# nexus5.net
KiCad netlist of a schematic drawn in Altium Designer
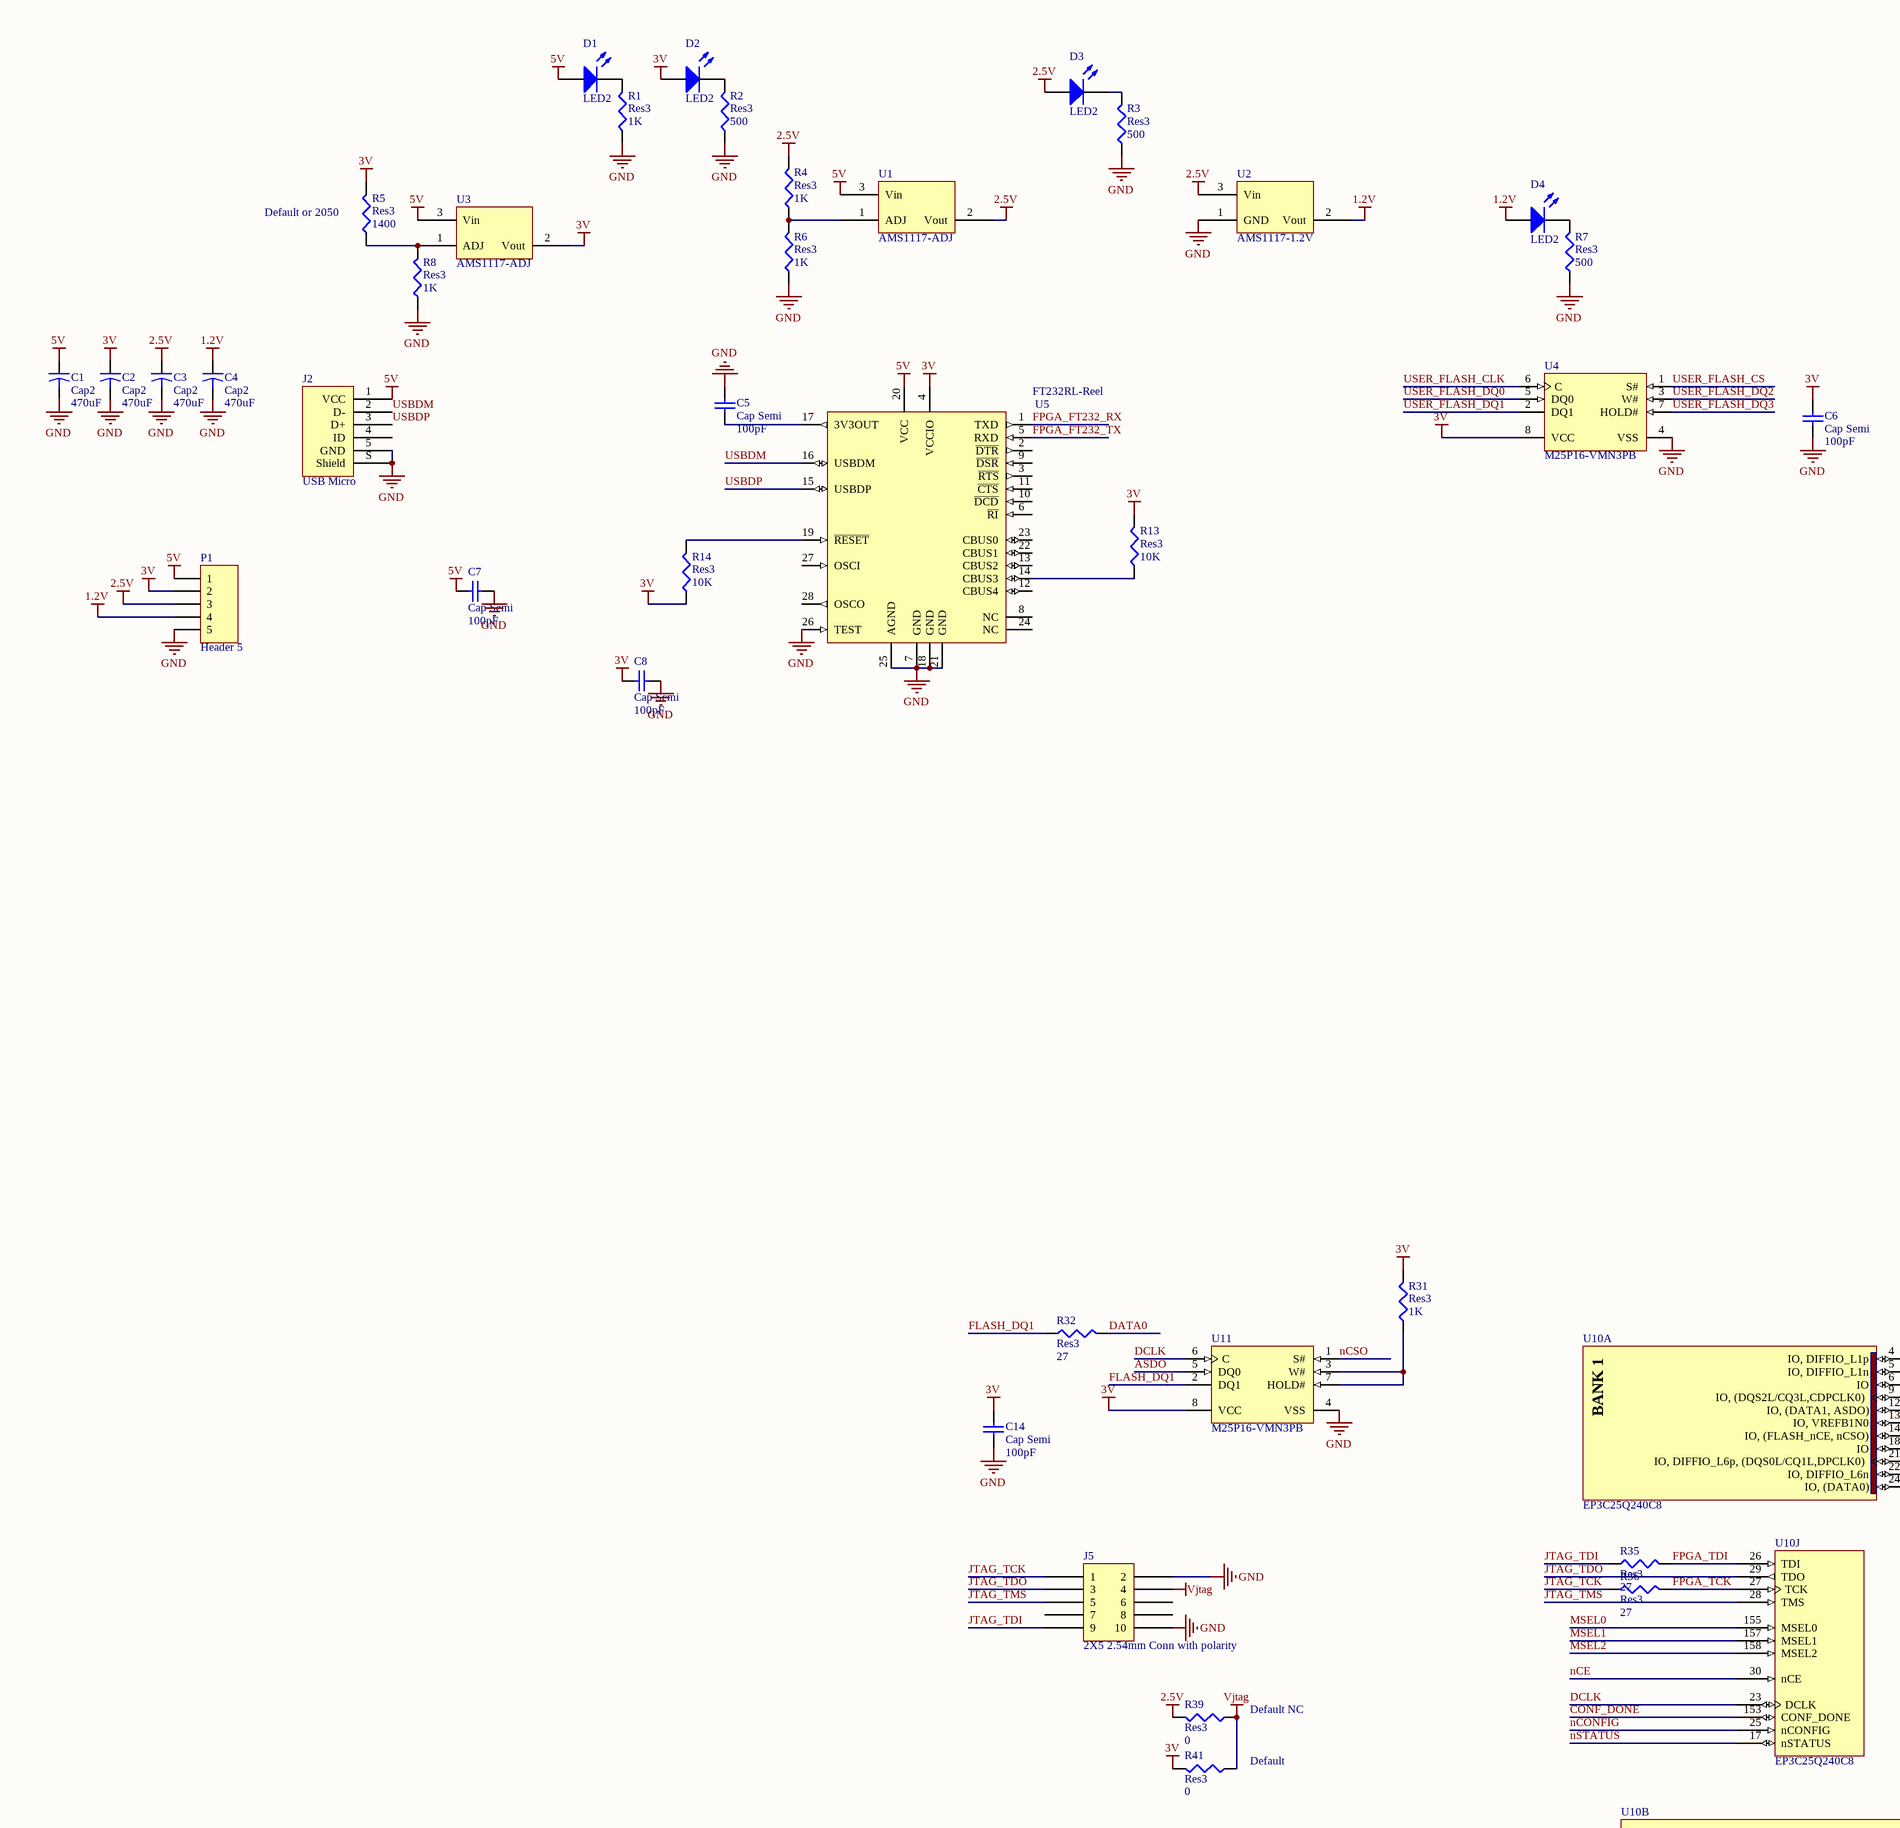
[diagram p0: nexus5.SchDoc, top left]
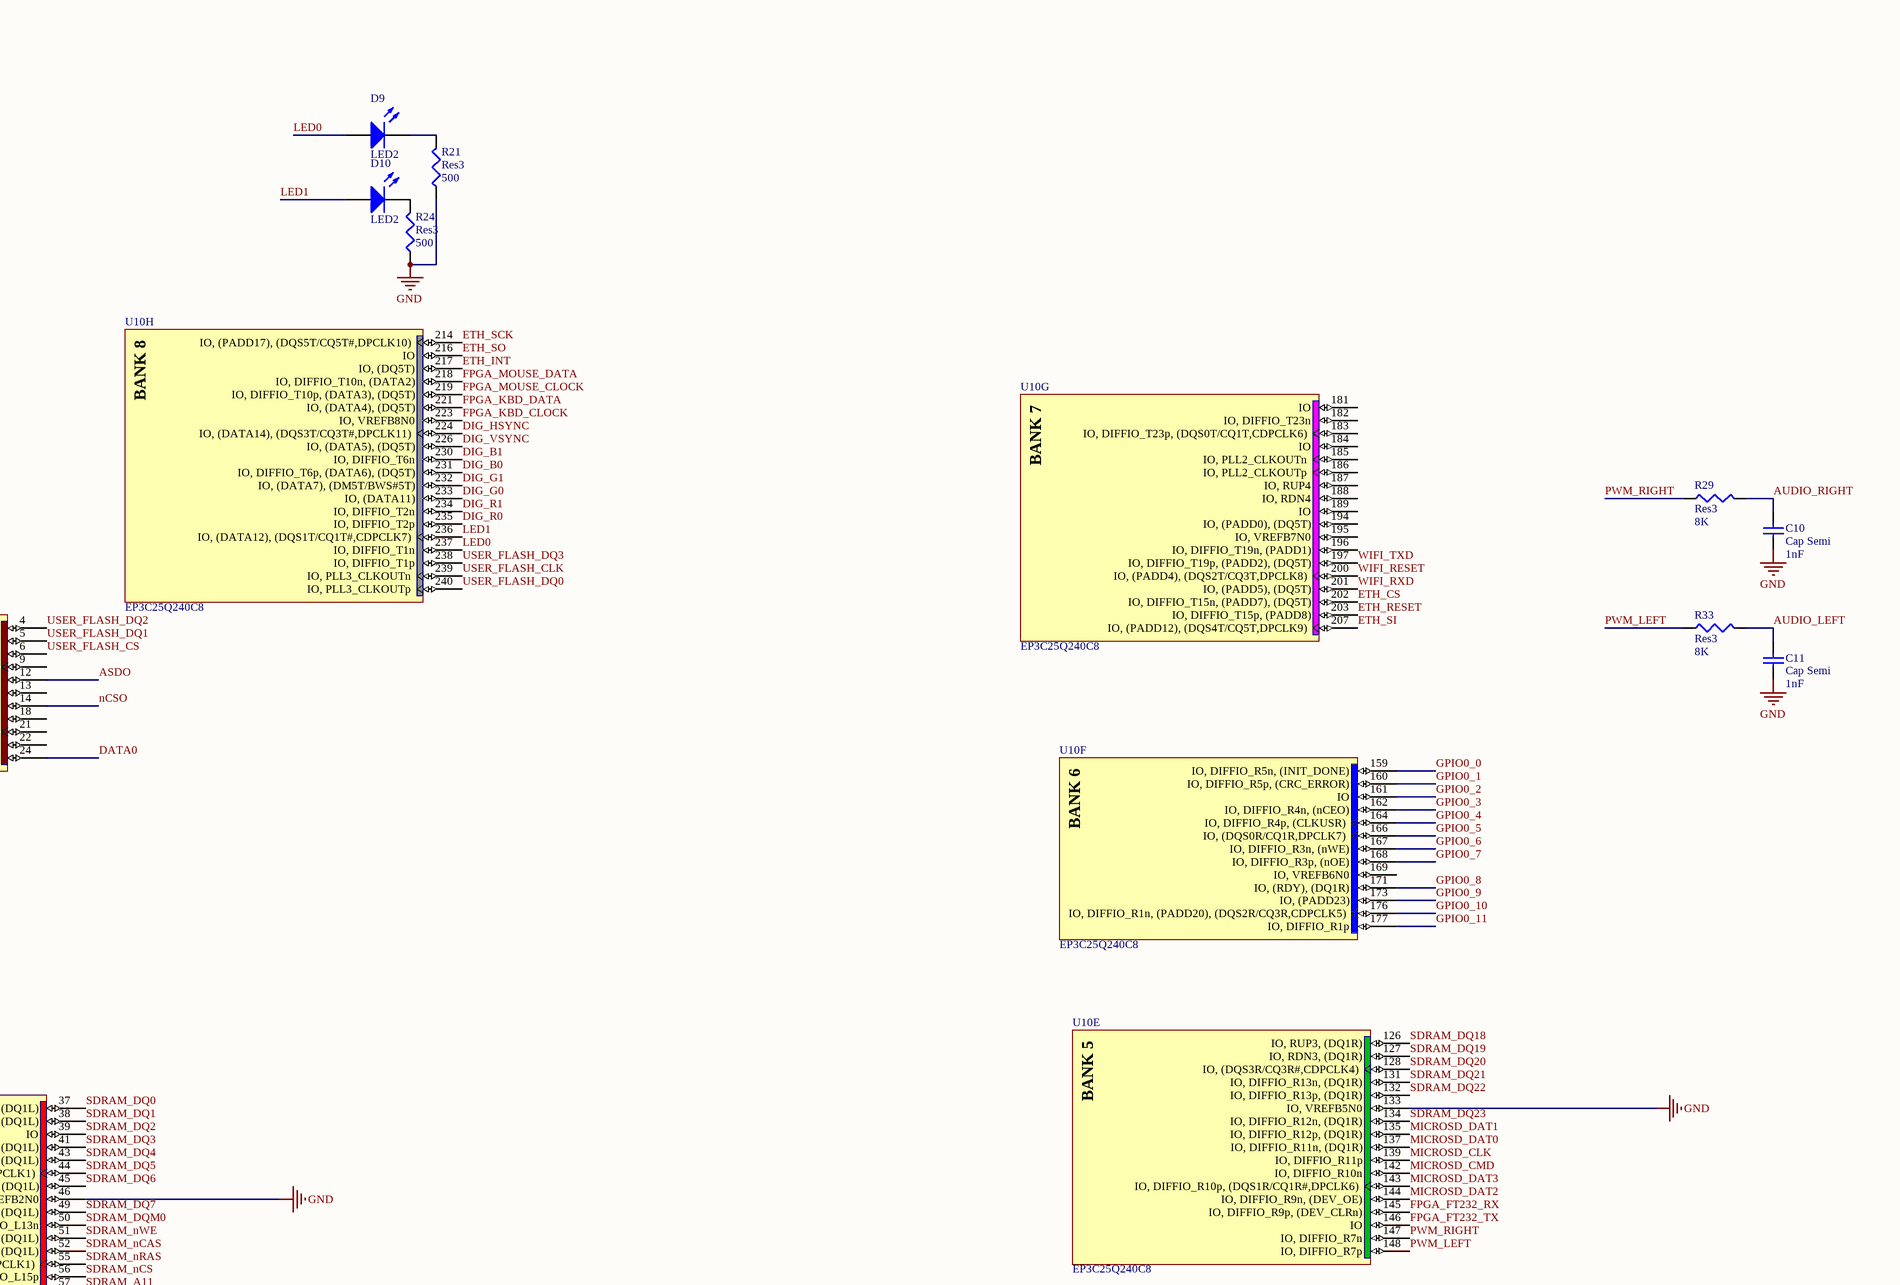
[diagram p1: nexus5.SchDoc, top middle]
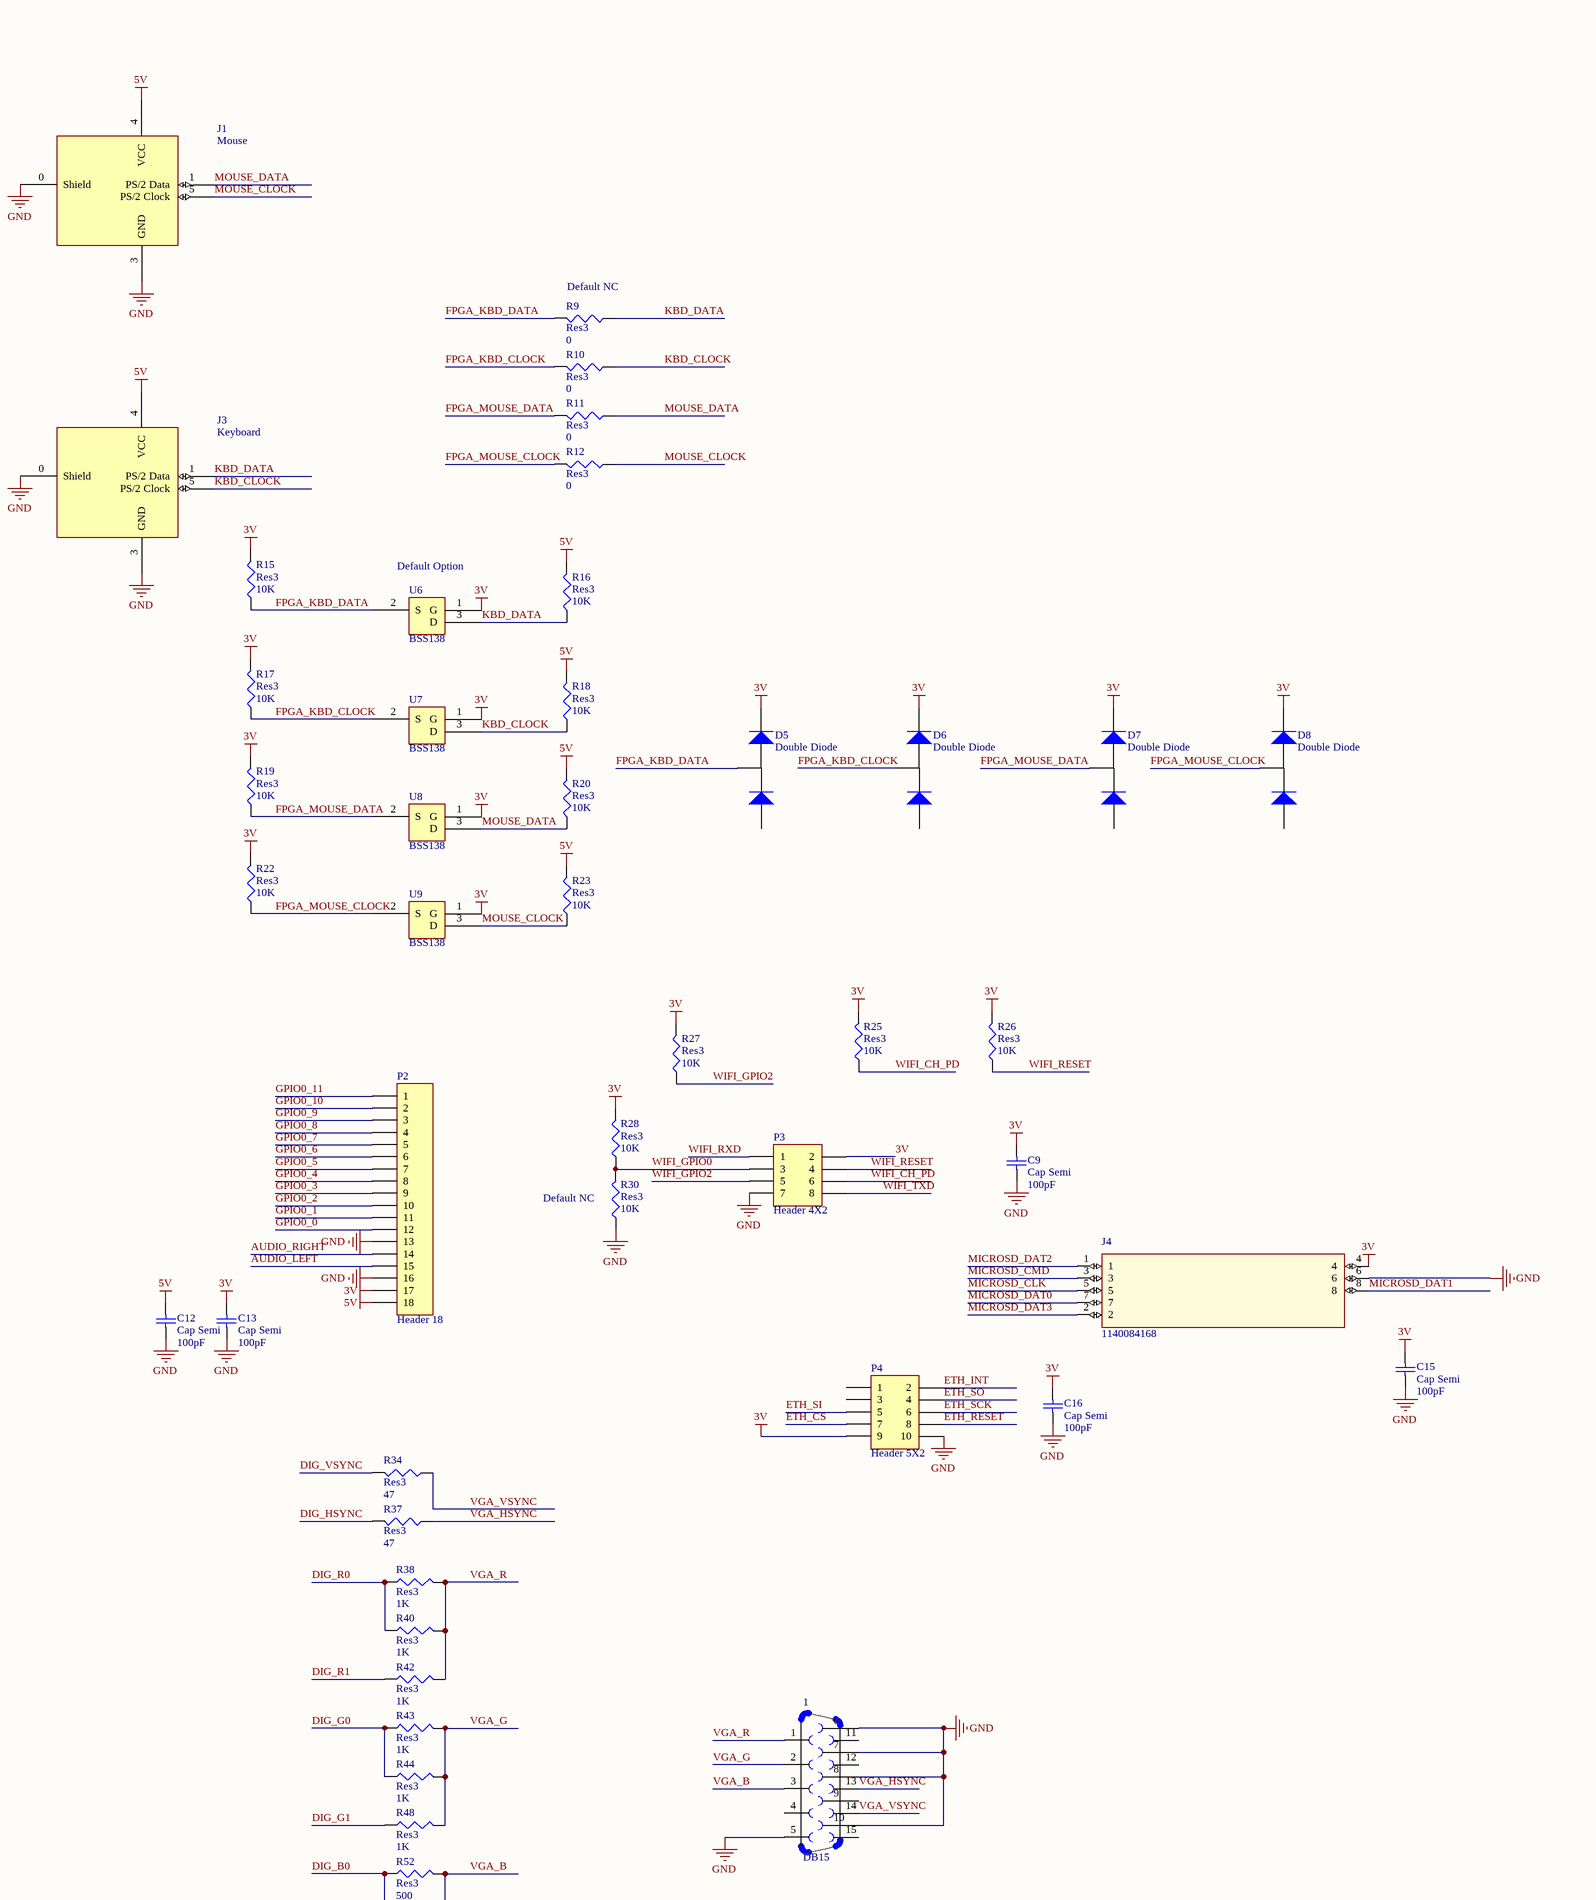
[diagram p2: nexus5.SchDoc, top right]
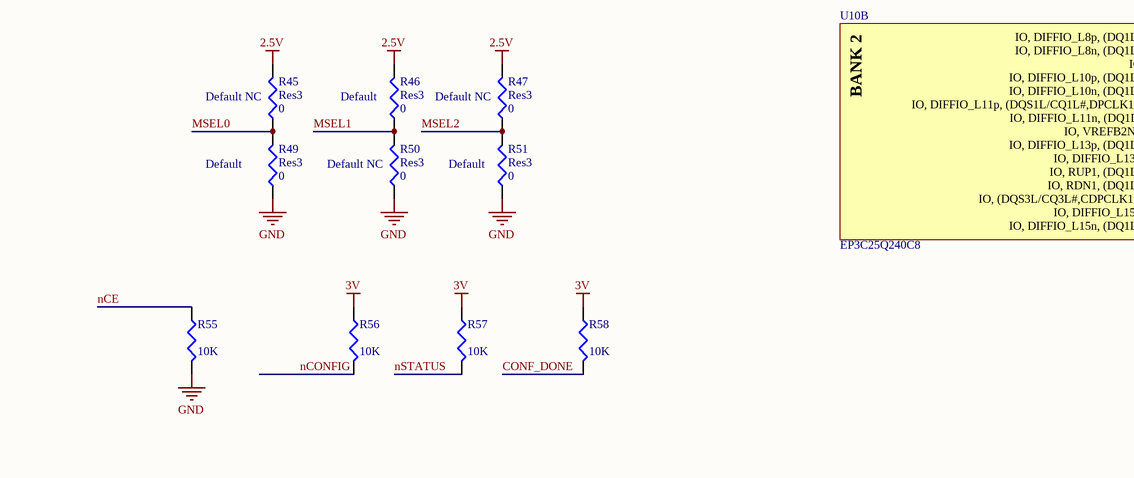
[diagram p3: nexus5.SchDoc, bottom left]
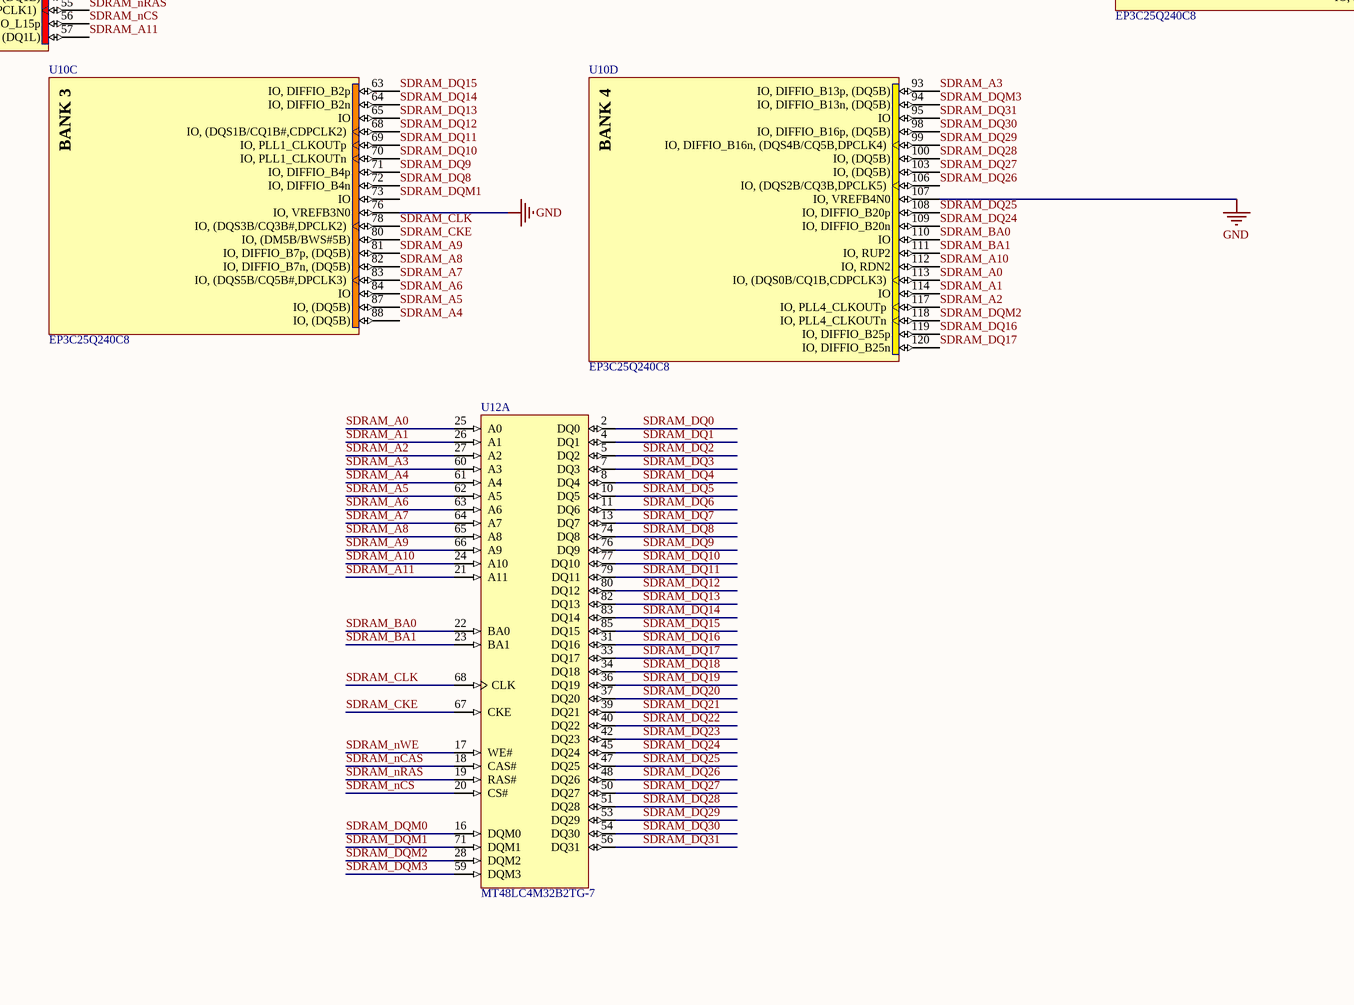
[diagram p4: nexus5.SchDoc, bottom middle]
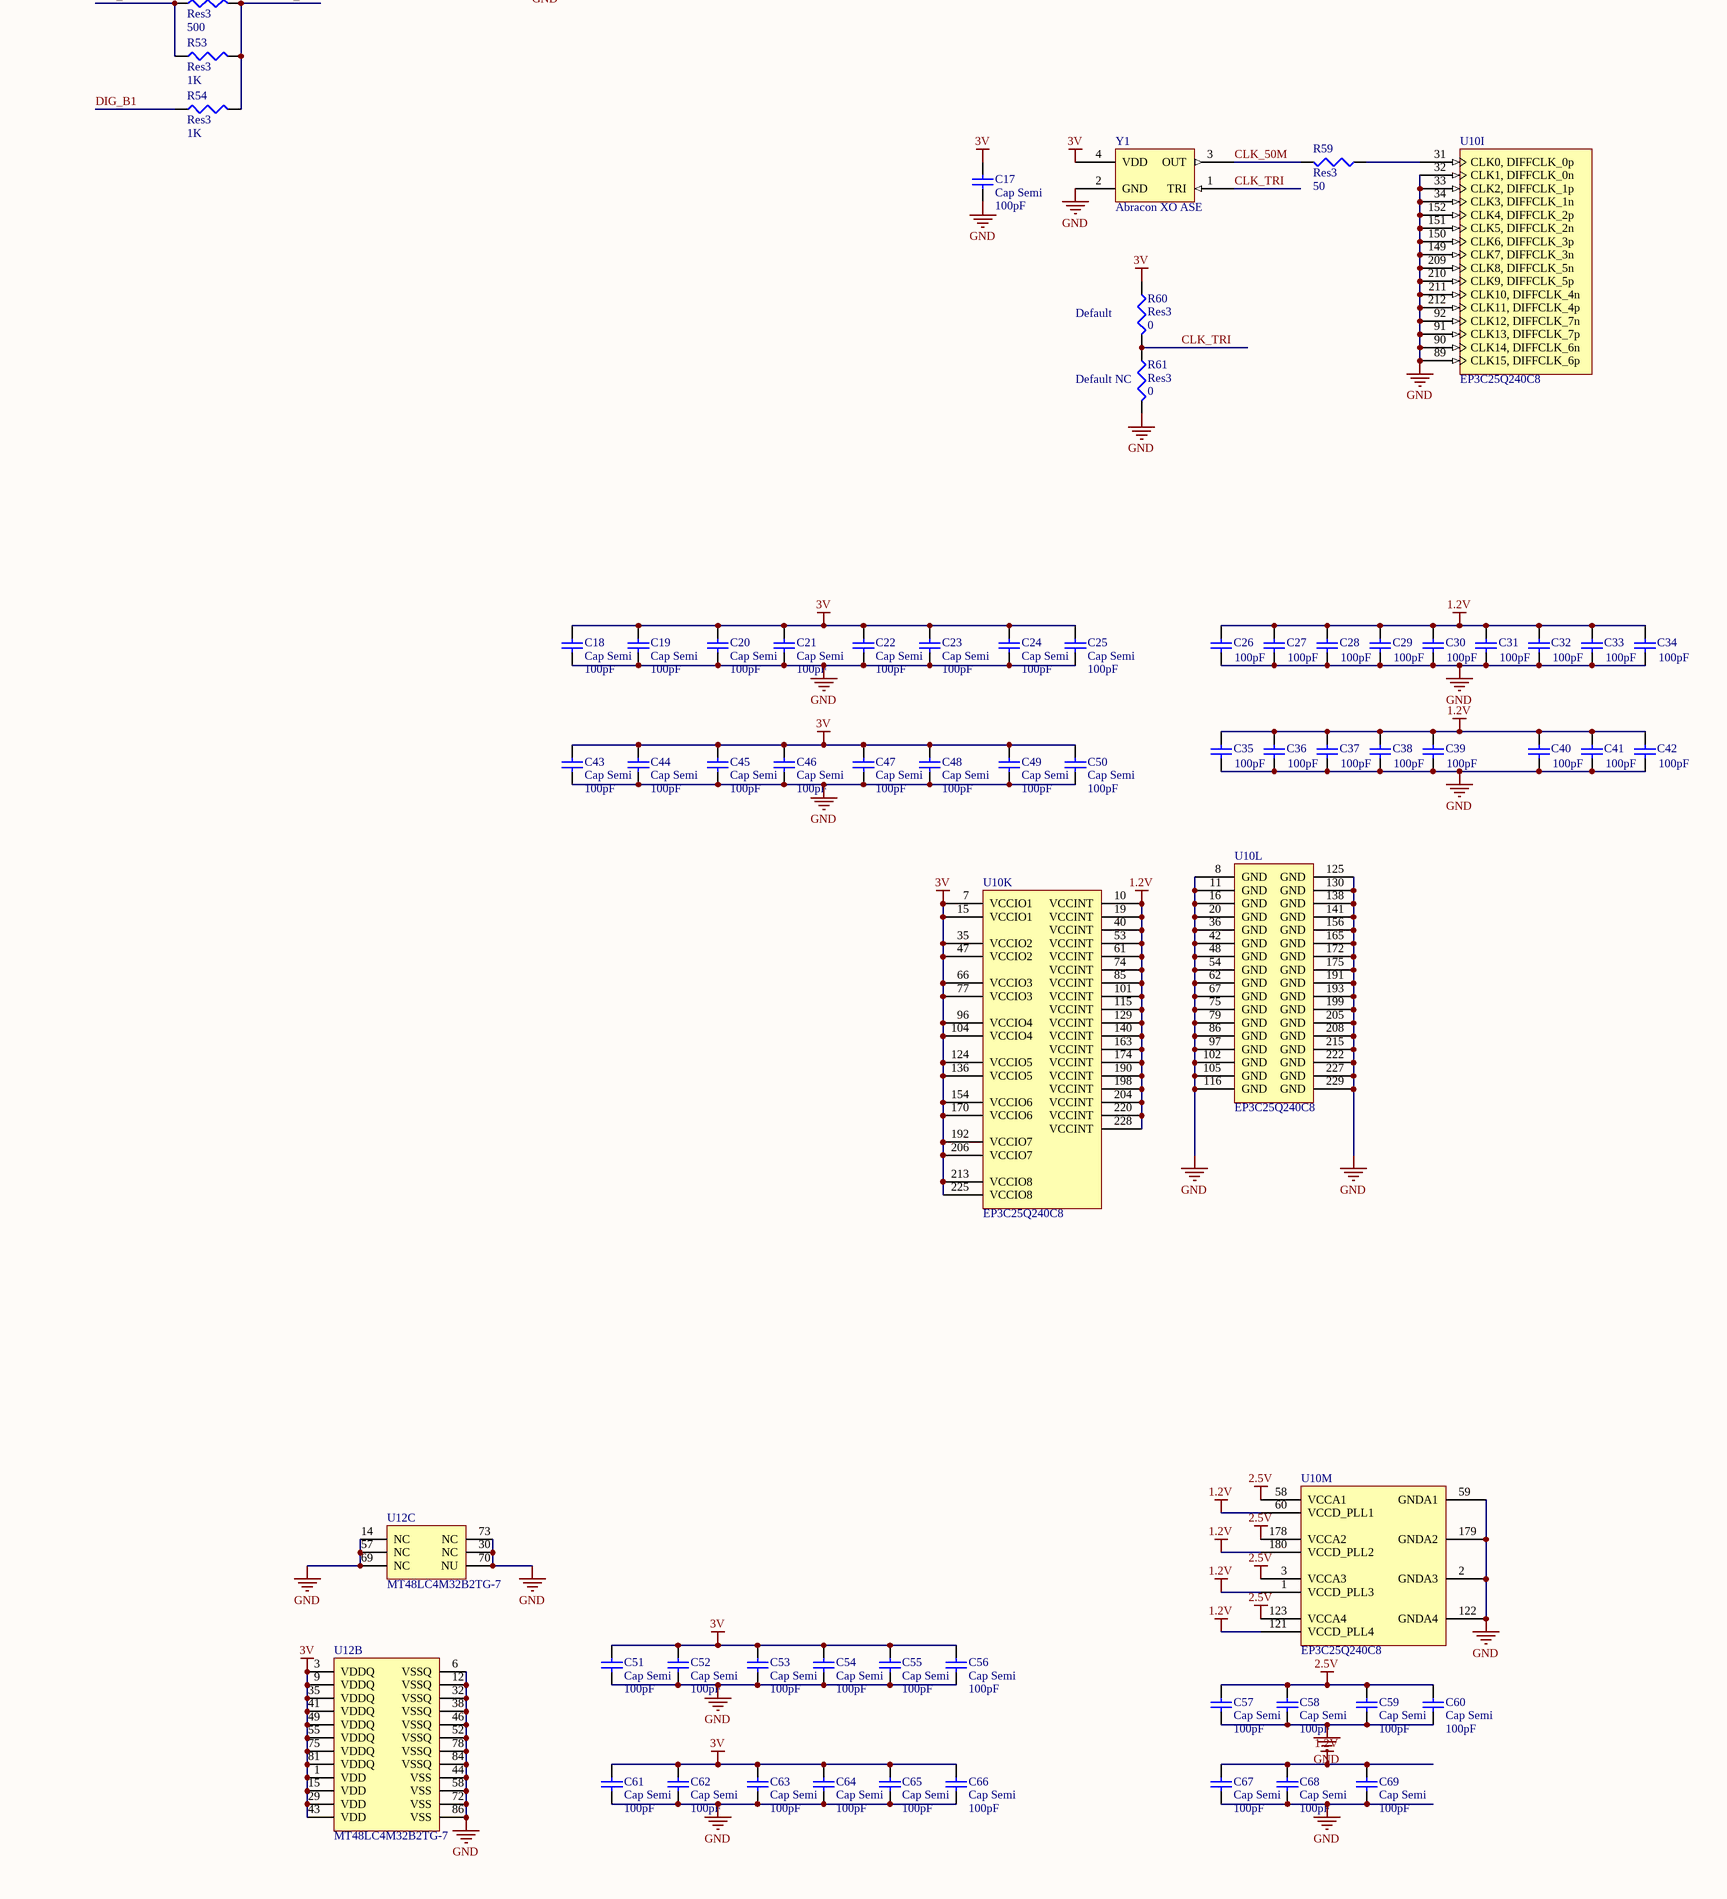
[diagram p5: nexus5.SchDoc, bottom right]

(export (version "E")
  (design (tool "Eeschema 10.0.6"))
  (components
    (comp (ref "1")
      (value "DB15")
      (footprint "*DB15")
      (description "Conn, f, 15rgb, 1 Piece")
      (fields (field (name "MF") "Belden Inc."))
      (libsource (lib "DB15") (part "DB15"))
    )
    (comp (ref "C1")
      (value "Cap2")
      (footprint "Small Cap Pol")
      (description "Capacitor")
      (fields (field (name "ALTIUM_VALUE") "470uF") (field (name "PUBLISHER") "Altium Limited"))
      (libsource (lib "Miscellaneous Devices") (part "Cap2"))
    )
    (comp (ref "C2")
      (value "Cap2")
      (footprint "Small Cap Pol")
      (description "Capacitor")
      (fields (field (name "ALTIUM_VALUE") "470uF") (field (name "PUBLISHER") "Altium Limited"))
      (libsource (lib "Miscellaneous Devices") (part "Cap2"))
    )
    (comp (ref "C3")
      (value "Cap2")
      (footprint "Small Cap Pol")
      (description "Capacitor")
      (fields (field (name "ALTIUM_VALUE") "470uF") (field (name "PUBLISHER") "Altium Limited"))
      (libsource (lib "Miscellaneous Devices") (part "Cap2"))
    )
    (comp (ref "C4")
      (value "Cap2")
      (footprint "Small Cap Pol")
      (description "Capacitor")
      (fields (field (name "ALTIUM_VALUE") "470uF") (field (name "PUBLISHER") "Altium Limited"))
      (libsource (lib "Miscellaneous Devices") (part "Cap2"))
    )
    (comp (ref "C5")
      (value "Cap Semi")
      (footprint "1608[0603]")
      (description "Capacitor (Semiconductor SIM Model)")
      (fields (field (name "ALTIUM_VALUE") "100pF") (field (name "PUBLISHER") "Altium Limited"))
      (libsource (lib "Miscellaneous Devices") (part "Cap Semi"))
    )
    (comp (ref "C6")
      (value "Cap Semi")
      (footprint "1608[0603]")
      (description "Capacitor (Semiconductor SIM Model)")
      (fields (field (name "ALTIUM_VALUE") "100pF") (field (name "PUBLISHER") "Altium Limited"))
      (libsource (lib "Miscellaneous Devices") (part "Cap Semi"))
    )
    (comp (ref "C7")
      (value "Cap Semi")
      (footprint "1608[0603]")
      (description "Capacitor (Semiconductor SIM Model)")
      (fields (field (name "ALTIUM_VALUE") "100pF") (field (name "PUBLISHER") "Altium Limited"))
      (libsource (lib "Miscellaneous Devices") (part "Cap Semi"))
    )
    (comp (ref "C8")
      (value "Cap Semi")
      (footprint "1608[0603]")
      (description "Capacitor (Semiconductor SIM Model)")
      (fields (field (name "ALTIUM_VALUE") "100pF") (field (name "PUBLISHER") "Altium Limited"))
      (libsource (lib "Miscellaneous Devices") (part "Cap Semi"))
    )
    (comp (ref "C9")
      (value "Cap Semi")
      (footprint "1608[0603]")
      (description "Capacitor (Semiconductor SIM Model)")
      (fields (field (name "ALTIUM_VALUE") "100pF") (field (name "PUBLISHER") "Altium Limited"))
      (libsource (lib "Miscellaneous Devices") (part "Cap Semi"))
    )
    (comp (ref "C10")
      (value "Cap Semi")
      (footprint "1608[0603]")
      (description "Capacitor (Semiconductor SIM Model)")
      (fields (field (name "ALTIUM_VALUE") "1nF") (field (name "PUBLISHER") "Altium Limited"))
      (libsource (lib "Miscellaneous Devices") (part "Cap Semi"))
    )
    (comp (ref "C11")
      (value "Cap Semi")
      (footprint "1608[0603]")
      (description "Capacitor (Semiconductor SIM Model)")
      (fields (field (name "ALTIUM_VALUE") "1nF") (field (name "PUBLISHER") "Altium Limited"))
      (libsource (lib "Miscellaneous Devices") (part "Cap Semi"))
    )
    (comp (ref "C12")
      (value "Cap Semi")
      (footprint "1608[0603]")
      (description "Capacitor (Semiconductor SIM Model)")
      (fields (field (name "ALTIUM_VALUE") "100pF") (field (name "PUBLISHER") "Altium Limited"))
      (libsource (lib "Miscellaneous Devices") (part "Cap Semi"))
    )
    (comp (ref "C13")
      (value "Cap Semi")
      (footprint "1608[0603]")
      (description "Capacitor (Semiconductor SIM Model)")
      (fields (field (name "ALTIUM_VALUE") "100pF") (field (name "PUBLISHER") "Altium Limited"))
      (libsource (lib "Miscellaneous Devices") (part "Cap Semi"))
    )
    (comp (ref "C14")
      (value "Cap Semi")
      (footprint "1608[0603]")
      (description "Capacitor (Semiconductor SIM Model)")
      (fields (field (name "ALTIUM_VALUE") "100pF") (field (name "PUBLISHER") "Altium Limited"))
      (libsource (lib "Miscellaneous Devices") (part "Cap Semi"))
    )
    (comp (ref "C15")
      (value "Cap Semi")
      (footprint "1608[0603]")
      (description "Capacitor (Semiconductor SIM Model)")
      (fields (field (name "ALTIUM_VALUE") "100pF") (field (name "PUBLISHER") "Altium Limited"))
      (libsource (lib "Miscellaneous Devices") (part "Cap Semi"))
    )
    (comp (ref "C16")
      (value "Cap Semi")
      (footprint "1608[0603]")
      (description "Capacitor (Semiconductor SIM Model)")
      (fields (field (name "ALTIUM_VALUE") "100pF") (field (name "PUBLISHER") "Altium Limited"))
      (libsource (lib "Miscellaneous Devices") (part "Cap Semi"))
    )
    (comp (ref "C17")
      (value "Cap Semi")
      (footprint "1608[0603]")
      (description "Capacitor (Semiconductor SIM Model)")
      (fields (field (name "ALTIUM_VALUE") "100pF") (field (name "PUBLISHER") "Altium Limited"))
      (libsource (lib "Miscellaneous Devices") (part "Cap Semi"))
    )
    (comp (ref "C18")
      (value "Cap Semi")
      (footprint "1608[0603]")
      (description "Capacitor (Semiconductor SIM Model)")
      (fields (field (name "ALTIUM_VALUE") "100pF") (field (name "PUBLISHER") "Altium Limited"))
      (libsource (lib "Miscellaneous Devices") (part "Cap Semi"))
    )
    (comp (ref "C19")
      (value "Cap Semi")
      (footprint "1608[0603]")
      (description "Capacitor (Semiconductor SIM Model)")
      (fields (field (name "ALTIUM_VALUE") "100pF") (field (name "PUBLISHER") "Altium Limited"))
      (libsource (lib "Miscellaneous Devices") (part "Cap Semi"))
    )
    (comp (ref "C20")
      (value "Cap Semi")
      (footprint "1608[0603]")
      (description "Capacitor (Semiconductor SIM Model)")
      (fields (field (name "ALTIUM_VALUE") "100pF") (field (name "PUBLISHER") "Altium Limited"))
      (libsource (lib "Miscellaneous Devices") (part "Cap Semi"))
    )
    (comp (ref "C21")
      (value "Cap Semi")
      (footprint "1608[0603]")
      (description "Capacitor (Semiconductor SIM Model)")
      (fields (field (name "ALTIUM_VALUE") "100pF") (field (name "PUBLISHER") "Altium Limited"))
      (libsource (lib "Miscellaneous Devices") (part "Cap Semi"))
    )
    (comp (ref "C22")
      (value "Cap Semi")
      (footprint "1608[0603]")
      (description "Capacitor (Semiconductor SIM Model)")
      (fields (field (name "ALTIUM_VALUE") "100pF") (field (name "PUBLISHER") "Altium Limited"))
      (libsource (lib "Miscellaneous Devices") (part "Cap Semi"))
    )
    (comp (ref "C23")
      (value "Cap Semi")
      (footprint "1608[0603]")
      (description "Capacitor (Semiconductor SIM Model)")
      (fields (field (name "ALTIUM_VALUE") "100pF") (field (name "PUBLISHER") "Altium Limited"))
      (libsource (lib "Miscellaneous Devices") (part "Cap Semi"))
    )
    (comp (ref "C24")
      (value "Cap Semi")
      (footprint "1608[0603]")
      (description "Capacitor (Semiconductor SIM Model)")
      (fields (field (name "ALTIUM_VALUE") "100pF") (field (name "PUBLISHER") "Altium Limited"))
      (libsource (lib "Miscellaneous Devices") (part "Cap Semi"))
    )
    (comp (ref "C25")
      (value "Cap Semi")
      (footprint "1608[0603]")
      (description "Capacitor (Semiconductor SIM Model)")
      (fields (field (name "ALTIUM_VALUE") "100pF") (field (name "PUBLISHER") "Altium Limited"))
      (libsource (lib "Miscellaneous Devices") (part "Cap Semi"))
    )
    (comp (ref "C26")
      (value "100pF")
      (footprint "1608[0603]")
      (description "Capacitor (Semiconductor SIM Model)")
      (fields (field (name "Comment") "Cap Semi") (field (name "PUBLISHER") "Altium Limited"))
      (libsource (lib "Miscellaneous Devices") (part "Cap Semi"))
    )
    (comp (ref "C27")
      (value "100pF")
      (footprint "1608[0603]")
      (description "Capacitor (Semiconductor SIM Model)")
      (fields (field (name "Comment") "Cap Semi") (field (name "PUBLISHER") "Altium Limited"))
      (libsource (lib "Miscellaneous Devices") (part "Cap Semi"))
    )
    (comp (ref "C28")
      (value "100pF")
      (footprint "1608[0603]")
      (description "Capacitor (Semiconductor SIM Model)")
      (fields (field (name "Comment") "Cap Semi") (field (name "PUBLISHER") "Altium Limited"))
      (libsource (lib "Miscellaneous Devices") (part "Cap Semi"))
    )
    (comp (ref "C29")
      (value "100pF")
      (footprint "1608[0603]")
      (description "Capacitor (Semiconductor SIM Model)")
      (fields (field (name "Comment") "Cap Semi") (field (name "PUBLISHER") "Altium Limited"))
      (libsource (lib "Miscellaneous Devices") (part "Cap Semi"))
    )
    (comp (ref "C30")
      (value "100pF")
      (footprint "1608[0603]")
      (description "Capacitor (Semiconductor SIM Model)")
      (fields (field (name "Comment") "Cap Semi") (field (name "PUBLISHER") "Altium Limited"))
      (libsource (lib "Miscellaneous Devices") (part "Cap Semi"))
    )
    (comp (ref "C31")
      (value "100pF")
      (footprint "1608[0603]")
      (description "Capacitor (Semiconductor SIM Model)")
      (fields (field (name "Comment") "Cap Semi") (field (name "PUBLISHER") "Altium Limited"))
      (libsource (lib "Miscellaneous Devices") (part "Cap Semi"))
    )
    (comp (ref "C32")
      (value "100pF")
      (footprint "1608[0603]")
      (description "Capacitor (Semiconductor SIM Model)")
      (fields (field (name "Comment") "Cap Semi") (field (name "PUBLISHER") "Altium Limited"))
      (libsource (lib "Miscellaneous Devices") (part "Cap Semi"))
    )
    (comp (ref "C33")
      (value "100pF")
      (footprint "1608[0603]")
      (description "Capacitor (Semiconductor SIM Model)")
      (fields (field (name "Comment") "Cap Semi") (field (name "PUBLISHER") "Altium Limited"))
      (libsource (lib "Miscellaneous Devices") (part "Cap Semi"))
    )
    (comp (ref "C34")
      (value "100pF")
      (footprint "1608[0603]")
      (description "Capacitor (Semiconductor SIM Model)")
      (fields (field (name "Comment") "Cap Semi") (field (name "PUBLISHER") "Altium Limited"))
      (libsource (lib "Miscellaneous Devices") (part "Cap Semi"))
    )
    (comp (ref "C35")
      (value "100pF")
      (footprint "1608[0603]")
      (description "Capacitor (Semiconductor SIM Model)")
      (fields (field (name "Comment") "Cap Semi") (field (name "PUBLISHER") "Altium Limited"))
      (libsource (lib "Miscellaneous Devices") (part "Cap Semi"))
    )
    (comp (ref "C36")
      (value "100pF")
      (footprint "1608[0603]")
      (description "Capacitor (Semiconductor SIM Model)")
      (fields (field (name "Comment") "Cap Semi") (field (name "PUBLISHER") "Altium Limited"))
      (libsource (lib "Miscellaneous Devices") (part "Cap Semi"))
    )
    (comp (ref "C37")
      (value "100pF")
      (footprint "1608[0603]")
      (description "Capacitor (Semiconductor SIM Model)")
      (fields (field (name "Comment") "Cap Semi") (field (name "PUBLISHER") "Altium Limited"))
      (libsource (lib "Miscellaneous Devices") (part "Cap Semi"))
    )
    (comp (ref "C38")
      (value "100pF")
      (footprint "1608[0603]")
      (description "Capacitor (Semiconductor SIM Model)")
      (fields (field (name "Comment") "Cap Semi") (field (name "PUBLISHER") "Altium Limited"))
      (libsource (lib "Miscellaneous Devices") (part "Cap Semi"))
    )
    (comp (ref "C39")
      (value "100pF")
      (footprint "1608[0603]")
      (description "Capacitor (Semiconductor SIM Model)")
      (fields (field (name "Comment") "Cap Semi") (field (name "PUBLISHER") "Altium Limited"))
      (libsource (lib "Miscellaneous Devices") (part "Cap Semi"))
    )
    (comp (ref "C40")
      (value "100pF")
      (footprint "1608[0603]")
      (description "Capacitor (Semiconductor SIM Model)")
      (fields (field (name "Comment") "Cap Semi") (field (name "PUBLISHER") "Altium Limited"))
      (libsource (lib "Miscellaneous Devices") (part "Cap Semi"))
    )
    (comp (ref "C41")
      (value "100pF")
      (footprint "1608[0603]")
      (description "Capacitor (Semiconductor SIM Model)")
      (fields (field (name "Comment") "Cap Semi") (field (name "PUBLISHER") "Altium Limited"))
      (libsource (lib "Miscellaneous Devices") (part "Cap Semi"))
    )
    (comp (ref "C42")
      (value "100pF")
      (footprint "1608[0603]")
      (description "Capacitor (Semiconductor SIM Model)")
      (fields (field (name "Comment") "Cap Semi") (field (name "PUBLISHER") "Altium Limited"))
      (libsource (lib "Miscellaneous Devices") (part "Cap Semi"))
    )
    (comp (ref "C43")
      (value "Cap Semi")
      (footprint "1608[0603]")
      (description "Capacitor (Semiconductor SIM Model)")
      (fields (field (name "ALTIUM_VALUE") "100pF") (field (name "PUBLISHER") "Altium Limited"))
      (libsource (lib "Miscellaneous Devices") (part "Cap Semi"))
    )
    (comp (ref "C44")
      (value "Cap Semi")
      (footprint "1608[0603]")
      (description "Capacitor (Semiconductor SIM Model)")
      (fields (field (name "ALTIUM_VALUE") "100pF") (field (name "PUBLISHER") "Altium Limited"))
      (libsource (lib "Miscellaneous Devices") (part "Cap Semi"))
    )
    (comp (ref "C45")
      (value "Cap Semi")
      (footprint "1608[0603]")
      (description "Capacitor (Semiconductor SIM Model)")
      (fields (field (name "ALTIUM_VALUE") "100pF") (field (name "PUBLISHER") "Altium Limited"))
      (libsource (lib "Miscellaneous Devices") (part "Cap Semi"))
    )
    (comp (ref "C46")
      (value "Cap Semi")
      (footprint "1608[0603]")
      (description "Capacitor (Semiconductor SIM Model)")
      (fields (field (name "ALTIUM_VALUE") "100pF") (field (name "PUBLISHER") "Altium Limited"))
      (libsource (lib "Miscellaneous Devices") (part "Cap Semi"))
    )
    (comp (ref "C47")
      (value "Cap Semi")
      (footprint "1608[0603]")
      (description "Capacitor (Semiconductor SIM Model)")
      (fields (field (name "ALTIUM_VALUE") "100pF") (field (name "PUBLISHER") "Altium Limited"))
      (libsource (lib "Miscellaneous Devices") (part "Cap Semi"))
    )
    (comp (ref "C48")
      (value "Cap Semi")
      (footprint "1608[0603]")
      (description "Capacitor (Semiconductor SIM Model)")
      (fields (field (name "ALTIUM_VALUE") "100pF") (field (name "PUBLISHER") "Altium Limited"))
      (libsource (lib "Miscellaneous Devices") (part "Cap Semi"))
    )
    (comp (ref "C49")
      (value "Cap Semi")
      (footprint "1608[0603]")
      (description "Capacitor (Semiconductor SIM Model)")
      (fields (field (name "ALTIUM_VALUE") "100pF") (field (name "PUBLISHER") "Altium Limited"))
      (libsource (lib "Miscellaneous Devices") (part "Cap Semi"))
    )
    (comp (ref "C50")
      (value "Cap Semi")
      (footprint "1608[0603]")
      (description "Capacitor (Semiconductor SIM Model)")
      (fields (field (name "ALTIUM_VALUE") "100pF") (field (name "PUBLISHER") "Altium Limited"))
      (libsource (lib "Miscellaneous Devices") (part "Cap Semi"))
    )
    (comp (ref "C51")
      (value "Cap Semi")
      (footprint "1608[0603]")
      (description "Capacitor (Semiconductor SIM Model)")
      (fields (field (name "ALTIUM_VALUE") "100pF") (field (name "PUBLISHER") "Altium Limited"))
      (libsource (lib "Miscellaneous Devices") (part "Cap Semi"))
    )
    (comp (ref "C52")
      (value "Cap Semi")
      (footprint "1608[0603]")
      (description "Capacitor (Semiconductor SIM Model)")
      (fields (field (name "ALTIUM_VALUE") "100pF") (field (name "PUBLISHER") "Altium Limited"))
      (libsource (lib "Miscellaneous Devices") (part "Cap Semi"))
    )
    (comp (ref "C53")
      (value "Cap Semi")
      (footprint "1608[0603]")
      (description "Capacitor (Semiconductor SIM Model)")
      (fields (field (name "ALTIUM_VALUE") "100pF") (field (name "PUBLISHER") "Altium Limited"))
      (libsource (lib "Miscellaneous Devices") (part "Cap Semi"))
    )
    (comp (ref "C54")
      (value "Cap Semi")
      (footprint "1608[0603]")
      (description "Capacitor (Semiconductor SIM Model)")
      (fields (field (name "ALTIUM_VALUE") "100pF") (field (name "PUBLISHER") "Altium Limited"))
      (libsource (lib "Miscellaneous Devices") (part "Cap Semi"))
    )
    (comp (ref "C55")
      (value "Cap Semi")
      (footprint "1608[0603]")
      (description "Capacitor (Semiconductor SIM Model)")
      (fields (field (name "ALTIUM_VALUE") "100pF") (field (name "PUBLISHER") "Altium Limited"))
      (libsource (lib "Miscellaneous Devices") (part "Cap Semi"))
    )
    (comp (ref "C56")
      (value "Cap Semi")
      (footprint "1608[0603]")
      (description "Capacitor (Semiconductor SIM Model)")
      (fields (field (name "ALTIUM_VALUE") "100pF") (field (name "PUBLISHER") "Altium Limited"))
      (libsource (lib "Miscellaneous Devices") (part "Cap Semi"))
    )
    (comp (ref "C57")
      (value "Cap Semi")
      (footprint "1608[0603]")
      (description "Capacitor (Semiconductor SIM Model)")
      (fields (field (name "ALTIUM_VALUE") "100pF") (field (name "PUBLISHER") "Altium Limited"))
      (libsource (lib "Miscellaneous Devices") (part "Cap Semi"))
    )
    (comp (ref "C58")
      (value "Cap Semi")
      (footprint "1608[0603]")
      (description "Capacitor (Semiconductor SIM Model)")
      (fields (field (name "ALTIUM_VALUE") "100pF") (field (name "PUBLISHER") "Altium Limited"))
      (libsource (lib "Miscellaneous Devices") (part "Cap Semi"))
    )
    (comp (ref "C59")
      (value "Cap Semi")
      (footprint "1608[0603]")
      (description "Capacitor (Semiconductor SIM Model)")
      (fields (field (name "ALTIUM_VALUE") "100pF") (field (name "PUBLISHER") "Altium Limited"))
      (libsource (lib "Miscellaneous Devices") (part "Cap Semi"))
    )
    (comp (ref "C60")
      (value "Cap Semi")
      (footprint "1608[0603]")
      (description "Capacitor (Semiconductor SIM Model)")
      (fields (field (name "ALTIUM_VALUE") "100pF") (field (name "PUBLISHER") "Altium Limited"))
      (libsource (lib "Miscellaneous Devices") (part "Cap Semi"))
    )
    (comp (ref "C61")
      (value "Cap Semi")
      (footprint "1608[0603]")
      (description "Capacitor (Semiconductor SIM Model)")
      (fields (field (name "ALTIUM_VALUE") "100pF") (field (name "PUBLISHER") "Altium Limited"))
      (libsource (lib "Miscellaneous Devices") (part "Cap Semi"))
    )
    (comp (ref "C62")
      (value "Cap Semi")
      (footprint "1608[0603]")
      (description "Capacitor (Semiconductor SIM Model)")
      (fields (field (name "ALTIUM_VALUE") "100pF") (field (name "PUBLISHER") "Altium Limited"))
      (libsource (lib "Miscellaneous Devices") (part "Cap Semi"))
    )
    (comp (ref "C63")
      (value "Cap Semi")
      (footprint "1608[0603]")
      (description "Capacitor (Semiconductor SIM Model)")
      (fields (field (name "ALTIUM_VALUE") "100pF") (field (name "PUBLISHER") "Altium Limited"))
      (libsource (lib "Miscellaneous Devices") (part "Cap Semi"))
    )
    (comp (ref "C64")
      (value "Cap Semi")
      (footprint "1608[0603]")
      (description "Capacitor (Semiconductor SIM Model)")
      (fields (field (name "ALTIUM_VALUE") "100pF") (field (name "PUBLISHER") "Altium Limited"))
      (libsource (lib "Miscellaneous Devices") (part "Cap Semi"))
    )
    (comp (ref "C65")
      (value "Cap Semi")
      (footprint "1608[0603]")
      (description "Capacitor (Semiconductor SIM Model)")
      (fields (field (name "ALTIUM_VALUE") "100pF") (field (name "PUBLISHER") "Altium Limited"))
      (libsource (lib "Miscellaneous Devices") (part "Cap Semi"))
    )
    (comp (ref "C66")
      (value "Cap Semi")
      (footprint "1608[0603]")
      (description "Capacitor (Semiconductor SIM Model)")
      (fields (field (name "ALTIUM_VALUE") "100pF") (field (name "PUBLISHER") "Altium Limited"))
      (libsource (lib "Miscellaneous Devices") (part "Cap Semi"))
    )
    (comp (ref "C67")
      (value "Cap Semi")
      (footprint "1608[0603]")
      (description "Capacitor (Semiconductor SIM Model)")
      (fields (field (name "ALTIUM_VALUE") "100pF") (field (name "PUBLISHER") "Altium Limited"))
      (libsource (lib "Miscellaneous Devices") (part "Cap Semi"))
    )
    (comp (ref "C68")
      (value "Cap Semi")
      (footprint "1608[0603]")
      (description "Capacitor (Semiconductor SIM Model)")
      (fields (field (name "ALTIUM_VALUE") "100pF") (field (name "PUBLISHER") "Altium Limited"))
      (libsource (lib "Miscellaneous Devices") (part "Cap Semi"))
    )
    (comp (ref "C69")
      (value "Cap Semi")
      (footprint "1608[0603]")
      (description "Capacitor (Semiconductor SIM Model)")
      (fields (field (name "ALTIUM_VALUE") "100pF") (field (name "PUBLISHER") "Altium Limited"))
      (libsource (lib "Miscellaneous Devices") (part "Cap Semi"))
    )
    (comp (ref "D1")
      (value "LED2")
      (footprint "3.2X1.6X1.1")
      (description "Typical RED, GREEN, YELLOW, AMBER GaAs LED")
      (fields (field (name "PUBLISHER") "Altium Limited"))
      (libsource (lib "Miscellaneous Devices") (part "LED2"))
    )
    (comp (ref "D2")
      (value "LED2")
      (footprint "3.2X1.6X1.1")
      (description "Typical RED, GREEN, YELLOW, AMBER GaAs LED")
      (fields (field (name "PUBLISHER") "Altium Limited"))
      (libsource (lib "Miscellaneous Devices") (part "LED2"))
    )
    (comp (ref "D3")
      (value "LED2")
      (footprint "3.2X1.6X1.1")
      (description "Typical RED, GREEN, YELLOW, AMBER GaAs LED")
      (fields (field (name "PUBLISHER") "Altium Limited"))
      (libsource (lib "Miscellaneous Devices") (part "LED2"))
    )
    (comp (ref "D4")
      (value "LED2")
      (footprint "3.2X1.6X1.1")
      (description "Typical RED, GREEN, YELLOW, AMBER GaAs LED")
      (fields (field (name "PUBLISHER") "Altium Limited"))
      (libsource (lib "Miscellaneous Devices") (part "LED2"))
    )
    (comp (ref "D5") (value "Double Diode") (footprint "SOT-23") (libsource (lib "BAT54S") (part "BAT54S")))
    (comp (ref "D6") (value "Double Diode") (footprint "SOT-23") (libsource (lib "BAT54S") (part "BAT54S")))
    (comp (ref "D7") (value "Double Diode") (footprint "SOT-23") (libsource (lib "BAT54S") (part "BAT54S")))
    (comp (ref "D8") (value "Double Diode") (footprint "SOT-23") (libsource (lib "BAT54S") (part "BAT54S")))
    (comp (ref "D9")
      (value "LED2")
      (footprint "3.2X1.6X1.1")
      (description "Typical RED, GREEN, YELLOW, AMBER GaAs LED")
      (fields (field (name "PUBLISHER") "Altium Limited"))
      (libsource (lib "Miscellaneous Devices") (part "LED2"))
    )
    (comp (ref "D10")
      (value "LED2")
      (footprint "3.2X1.6X1.1")
      (description "Typical RED, GREEN, YELLOW, AMBER GaAs LED")
      (fields (field (name "PUBLISHER") "Altium Limited"))
      (libsource (lib "Miscellaneous Devices") (part "LED2"))
    )
    (comp (ref "J1") (value "Mouse") (footprint "MD-60S") (libsource (lib "PSslash2") (part "MD60S")))
    (comp (ref "J2")
      (value "USB Micro")
      (footprint "FCI USB 10118193-0001LF")
      (libsource (lib "MicroUSB") (part "USB 2.0 Type B Micro"))
    )
    (comp (ref "J3") (value "Keyboard") (footprint "MD-60S") (libsource (lib "PSslash2") (part "MD60S")))
    (comp (ref "J4")
      (value "1140084168")
      (footprint "1140084168")
      (description "Memory Card Connector, Microsd, 8 Position, Full Reel")
      (fields (field (name "DIGI-KEY_PART_NUMBER") "114-00841-68-1-ND") (field (name "MF") "Amphenol ICC"))
      (libsource (lib "1140084168") (part "1140084168"))
    )
    (comp (ref "J5")
      (value "2X5 2.54mm Conn with polarity")
      (footprint "2X5 with polarity")
      (libsource (lib "Corner") (part "2X5 2.54mm Conn with polarity"))
    )
    (comp (ref "P1")
      (value "Header 5")
      (footprint "HDR1X5")
      (description "Header, 5-Pin")
      (fields (field (name "PUBLISHER") "Altium Limited"))
      (libsource (lib "Miscellaneous Connectors") (part "Header 5"))
    )
    (comp (ref "P2")
      (value "Header 18")
      (footprint "HDR1X18")
      (description "Header, 18-Pin")
      (fields (field (name "PUBLISHER") "Altium Limited"))
      (libsource (lib "Miscellaneous Connectors") (part "Header 18"))
    )
    (comp (ref "P3")
      (value "Header 4X2")
      (footprint "HDR2X4")
      (description "Header, 4-Pin, Dual row")
      (fields (field (name "PUBLISHER") "Altium Limited"))
      (libsource (lib "Miscellaneous Connectors") (part "Header 4X2"))
    )
    (comp (ref "P4")
      (value "Header 5X2")
      (footprint "HDR2X5")
      (description "Header, 5-Pin, Dual row")
      (fields (field (name "PUBLISHER") "Altium Limited"))
      (libsource (lib "Miscellaneous Connectors") (part "Header 5X2"))
    )
    (comp (ref "R1")
      (value "Res3")
      (footprint "J1-0603")
      (description "Resistor")
      (fields (field (name "ALTIUM_VALUE") "1K") (field (name "PUBLISHER") "Altium Limited"))
      (libsource (lib "Miscellaneous Devices") (part "Res3"))
    )
    (comp (ref "R2")
      (value "Res3")
      (footprint "J1-0603")
      (description "Resistor")
      (fields (field (name "ALTIUM_VALUE") "500") (field (name "PUBLISHER") "Altium Limited"))
      (libsource (lib "Miscellaneous Devices") (part "Res3"))
    )
    (comp (ref "R3")
      (value "Res3")
      (footprint "J1-0603")
      (description "Resistor")
      (fields (field (name "ALTIUM_VALUE") "500") (field (name "PUBLISHER") "Altium Limited"))
      (libsource (lib "Miscellaneous Devices") (part "Res3"))
    )
    (comp (ref "R4")
      (value "Res3")
      (footprint "J1-0603")
      (description "Resistor")
      (fields (field (name "ALTIUM_VALUE") "1K") (field (name "PUBLISHER") "Altium Limited"))
      (libsource (lib "Miscellaneous Devices") (part "Res3"))
    )
    (comp (ref "R5")
      (value "Res3")
      (footprint "J1-0603")
      (description "Resistor")
      (fields (field (name "ALTIUM_VALUE") "1400") (field (name "PUBLISHER") "Altium Limited"))
      (libsource (lib "Miscellaneous Devices") (part "Res3"))
    )
    (comp (ref "R6")
      (value "Res3")
      (footprint "J1-0603")
      (description "Resistor")
      (fields (field (name "ALTIUM_VALUE") "1K") (field (name "PUBLISHER") "Altium Limited"))
      (libsource (lib "Miscellaneous Devices") (part "Res3"))
    )
    (comp (ref "R7")
      (value "Res3")
      (footprint "J1-0603")
      (description "Resistor")
      (fields (field (name "ALTIUM_VALUE") "500") (field (name "PUBLISHER") "Altium Limited"))
      (libsource (lib "Miscellaneous Devices") (part "Res3"))
    )
    (comp (ref "R8")
      (value "Res3")
      (footprint "J1-0603")
      (description "Resistor")
      (fields (field (name "ALTIUM_VALUE") "1K") (field (name "PUBLISHER") "Altium Limited"))
      (libsource (lib "Miscellaneous Devices") (part "Res3"))
    )
    (comp (ref "R9")
      (value "Res3")
      (footprint "J1-0603")
      (description "Resistor")
      (fields (field (name "ALTIUM_VALUE") "0") (field (name "PUBLISHER") "Altium Limited"))
      (libsource (lib "Miscellaneous Devices") (part "Res3"))
    )
    (comp (ref "R10")
      (value "Res3")
      (footprint "J1-0603")
      (description "Resistor")
      (fields (field (name "ALTIUM_VALUE") "0") (field (name "PUBLISHER") "Altium Limited"))
      (libsource (lib "Miscellaneous Devices") (part "Res3"))
    )
    (comp (ref "R11")
      (value "Res3")
      (footprint "J1-0603")
      (description "Resistor")
      (fields (field (name "ALTIUM_VALUE") "0") (field (name "PUBLISHER") "Altium Limited"))
      (libsource (lib "Miscellaneous Devices") (part "Res3"))
    )
    (comp (ref "R12")
      (value "Res3")
      (footprint "J1-0603")
      (description "Resistor")
      (fields (field (name "ALTIUM_VALUE") "0") (field (name "PUBLISHER") "Altium Limited"))
      (libsource (lib "Miscellaneous Devices") (part "Res3"))
    )
    (comp (ref "R13")
      (value "Res3")
      (footprint "J1-0603")
      (description "Resistor")
      (fields (field (name "ALTIUM_VALUE") "10K") (field (name "PUBLISHER") "Altium Limited"))
      (libsource (lib "Miscellaneous Devices") (part "Res3"))
    )
    (comp (ref "R14")
      (value "Res3")
      (footprint "J1-0603")
      (description "Resistor")
      (fields (field (name "ALTIUM_VALUE") "10K") (field (name "PUBLISHER") "Altium Limited"))
      (libsource (lib "Miscellaneous Devices") (part "Res3"))
    )
    (comp (ref "R15")
      (value "Res3")
      (footprint "J1-0603")
      (description "Resistor")
      (fields (field (name "ALTIUM_VALUE") "10K") (field (name "PUBLISHER") "Altium Limited"))
      (libsource (lib "Miscellaneous Devices") (part "Res3"))
    )
    (comp (ref "R16")
      (value "Res3")
      (footprint "J1-0603")
      (description "Resistor")
      (fields (field (name "ALTIUM_VALUE") "10K") (field (name "PUBLISHER") "Altium Limited"))
      (libsource (lib "Miscellaneous Devices") (part "Res3"))
    )
    (comp (ref "R17")
      (value "Res3")
      (footprint "J1-0603")
      (description "Resistor")
      (fields (field (name "ALTIUM_VALUE") "10K") (field (name "PUBLISHER") "Altium Limited"))
      (libsource (lib "Miscellaneous Devices") (part "Res3"))
    )
    (comp (ref "R18")
      (value "Res3")
      (footprint "J1-0603")
      (description "Resistor")
      (fields (field (name "ALTIUM_VALUE") "10K") (field (name "PUBLISHER") "Altium Limited"))
      (libsource (lib "Miscellaneous Devices") (part "Res3"))
    )
    (comp (ref "R19")
      (value "Res3")
      (footprint "J1-0603")
      (description "Resistor")
      (fields (field (name "ALTIUM_VALUE") "10K") (field (name "PUBLISHER") "Altium Limited"))
      (libsource (lib "Miscellaneous Devices") (part "Res3"))
    )
    (comp (ref "R20")
      (value "Res3")
      (footprint "J1-0603")
      (description "Resistor")
      (fields (field (name "ALTIUM_VALUE") "10K") (field (name "PUBLISHER") "Altium Limited"))
      (libsource (lib "Miscellaneous Devices") (part "Res3"))
    )
    (comp (ref "R21")
      (value "Res3")
      (footprint "J1-0603")
      (description "Resistor")
      (fields (field (name "ALTIUM_VALUE") "500") (field (name "PUBLISHER") "Altium Limited"))
      (libsource (lib "Miscellaneous Devices") (part "Res3"))
    )
    (comp (ref "R22")
      (value "Res3")
      (footprint "J1-0603")
      (description "Resistor")
      (fields (field (name "ALTIUM_VALUE") "10K") (field (name "PUBLISHER") "Altium Limited"))
      (libsource (lib "Miscellaneous Devices") (part "Res3"))
    )
    (comp (ref "R23")
      (value "Res3")
      (footprint "J1-0603")
      (description "Resistor")
      (fields (field (name "ALTIUM_VALUE") "10K") (field (name "PUBLISHER") "Altium Limited"))
      (libsource (lib "Miscellaneous Devices") (part "Res3"))
    )
    (comp (ref "R24")
      (value "Res3")
      (footprint "J1-0603")
      (description "Resistor")
      (fields (field (name "ALTIUM_VALUE") "500") (field (name "PUBLISHER") "Altium Limited"))
      (libsource (lib "Miscellaneous Devices") (part "Res3"))
    )
    (comp (ref "R25")
      (value "Res3")
      (footprint "J1-0603")
      (description "Resistor")
      (fields (field (name "ALTIUM_VALUE") "10K") (field (name "PUBLISHER") "Altium Limited"))
      (libsource (lib "Miscellaneous Devices") (part "Res3"))
    )
    (comp (ref "R26")
      (value "Res3")
      (footprint "J1-0603")
      (description "Resistor")
      (fields (field (name "ALTIUM_VALUE") "10K") (field (name "PUBLISHER") "Altium Limited"))
      (libsource (lib "Miscellaneous Devices") (part "Res3"))
    )
    (comp (ref "R27")
      (value "Res3")
      (footprint "J1-0603")
      (description "Resistor")
      (fields (field (name "ALTIUM_VALUE") "10K") (field (name "PUBLISHER") "Altium Limited"))
      (libsource (lib "Miscellaneous Devices") (part "Res3"))
    )
    (comp (ref "R28")
      (value "Res3")
      (footprint "J1-0603")
      (description "Resistor")
      (fields (field (name "ALTIUM_VALUE") "10K") (field (name "PUBLISHER") "Altium Limited"))
      (libsource (lib "Miscellaneous Devices") (part "Res3"))
    )
    (comp (ref "R29")
      (value "Res3")
      (footprint "J1-0603")
      (description "Resistor")
      (fields (field (name "ALTIUM_VALUE") "8K") (field (name "PUBLISHER") "Altium Limited"))
      (libsource (lib "Miscellaneous Devices") (part "Res3"))
    )
    (comp (ref "R30")
      (value "Res3")
      (footprint "J1-0603")
      (description "Resistor")
      (fields (field (name "ALTIUM_VALUE") "10K") (field (name "PUBLISHER") "Altium Limited"))
      (libsource (lib "Miscellaneous Devices") (part "Res3"))
    )
    (comp (ref "R31")
      (value "Res3")
      (footprint "J1-0603")
      (description "Resistor")
      (fields (field (name "ALTIUM_VALUE") "1K") (field (name "PUBLISHER") "Altium Limited"))
      (libsource (lib "Miscellaneous Devices") (part "Res3"))
    )
    (comp (ref "R32")
      (value "Res3")
      (footprint "J1-0603")
      (description "Resistor")
      (fields (field (name "ALTIUM_VALUE") "27") (field (name "PUBLISHER") "Altium Limited"))
      (libsource (lib "Miscellaneous Devices") (part "Res3"))
    )
    (comp (ref "R33")
      (value "Res3")
      (footprint "J1-0603")
      (description "Resistor")
      (fields (field (name "ALTIUM_VALUE") "8K") (field (name "PUBLISHER") "Altium Limited"))
      (libsource (lib "Miscellaneous Devices") (part "Res3"))
    )
    (comp (ref "R34")
      (value "Res3")
      (footprint "J1-0603")
      (description "Resistor")
      (fields (field (name "ALTIUM_VALUE") "47") (field (name "PUBLISHER") "Altium Limited"))
      (libsource (lib "Miscellaneous Devices") (part "Res3"))
    )
    (comp (ref "R35")
      (value "Res3")
      (footprint "J1-0603")
      (description "Resistor")
      (fields (field (name "ALTIUM_VALUE") "27") (field (name "PUBLISHER") "Altium Limited"))
      (libsource (lib "Miscellaneous Devices") (part "Res3"))
    )
    (comp (ref "R36")
      (value "Res3")
      (footprint "J1-0603")
      (description "Resistor")
      (fields (field (name "ALTIUM_VALUE") "27") (field (name "PUBLISHER") "Altium Limited"))
      (libsource (lib "Miscellaneous Devices") (part "Res3"))
    )
    (comp (ref "R37")
      (value "Res3")
      (footprint "J1-0603")
      (description "Resistor")
      (fields (field (name "ALTIUM_VALUE") "47") (field (name "PUBLISHER") "Altium Limited"))
      (libsource (lib "Miscellaneous Devices") (part "Res3"))
    )
    (comp (ref "R38")
      (value "Res3")
      (footprint "J1-0603")
      (description "Resistor")
      (fields (field (name "ALTIUM_VALUE") "1K") (field (name "PUBLISHER") "Altium Limited"))
      (libsource (lib "Miscellaneous Devices") (part "Res3"))
    )
    (comp (ref "R39")
      (value "Res3")
      (footprint "J1-0603")
      (description "Resistor")
      (fields (field (name "ALTIUM_VALUE") "0") (field (name "PUBLISHER") "Altium Limited"))
      (libsource (lib "Miscellaneous Devices") (part "Res3"))
    )
    (comp (ref "R40")
      (value "Res3")
      (footprint "J1-0603")
      (description "Resistor")
      (fields (field (name "ALTIUM_VALUE") "1K") (field (name "PUBLISHER") "Altium Limited"))
      (libsource (lib "Miscellaneous Devices") (part "Res3"))
    )
    (comp (ref "R41")
      (value "Res3")
      (footprint "J1-0603")
      (description "Resistor")
      (fields (field (name "ALTIUM_VALUE") "0") (field (name "PUBLISHER") "Altium Limited"))
      (libsource (lib "Miscellaneous Devices") (part "Res3"))
    )
    (comp (ref "R42")
      (value "Res3")
      (footprint "J1-0603")
      (description "Resistor")
      (fields (field (name "ALTIUM_VALUE") "1K") (field (name "PUBLISHER") "Altium Limited"))
      (libsource (lib "Miscellaneous Devices") (part "Res3"))
    )
    (comp (ref "R43")
      (value "Res3")
      (footprint "J1-0603")
      (description "Resistor")
      (fields (field (name "ALTIUM_VALUE") "1K") (field (name "PUBLISHER") "Altium Limited"))
      (libsource (lib "Miscellaneous Devices") (part "Res3"))
    )
    (comp (ref "R44")
      (value "Res3")
      (footprint "J1-0603")
      (description "Resistor")
      (fields (field (name "ALTIUM_VALUE") "1K") (field (name "PUBLISHER") "Altium Limited"))
      (libsource (lib "Miscellaneous Devices") (part "Res3"))
    )
    (comp (ref "R45")
      (value "Res3")
      (footprint "J1-0603")
      (description "Resistor")
      (fields (field (name "ALTIUM_VALUE") "0") (field (name "PUBLISHER") "Altium Limited"))
      (libsource (lib "Miscellaneous Devices") (part "Res3"))
    )
    (comp (ref "R46")
      (value "Res3")
      (footprint "J1-0603")
      (description "Resistor")
      (fields (field (name "ALTIUM_VALUE") "0") (field (name "PUBLISHER") "Altium Limited"))
      (libsource (lib "Miscellaneous Devices") (part "Res3"))
    )
    (comp (ref "R47")
      (value "Res3")
      (footprint "J1-0603")
      (description "Resistor")
      (fields (field (name "ALTIUM_VALUE") "0") (field (name "PUBLISHER") "Altium Limited"))
      (libsource (lib "Miscellaneous Devices") (part "Res3"))
    )
    (comp (ref "R48")
      (value "Res3")
      (footprint "J1-0603")
      (description "Resistor")
      (fields (field (name "ALTIUM_VALUE") "1K") (field (name "PUBLISHER") "Altium Limited"))
      (libsource (lib "Miscellaneous Devices") (part "Res3"))
    )
    (comp (ref "R49")
      (value "Res3")
      (footprint "J1-0603")
      (description "Resistor")
      (fields (field (name "ALTIUM_VALUE") "0") (field (name "PUBLISHER") "Altium Limited"))
      (libsource (lib "Miscellaneous Devices") (part "Res3"))
    )
    (comp (ref "R50")
      (value "Res3")
      (footprint "J1-0603")
      (description "Resistor")
      (fields (field (name "ALTIUM_VALUE") "0") (field (name "PUBLISHER") "Altium Limited"))
      (libsource (lib "Miscellaneous Devices") (part "Res3"))
    )
    (comp (ref "R51")
      (value "Res3")
      (footprint "J1-0603")
      (description "Resistor")
      (fields (field (name "ALTIUM_VALUE") "0") (field (name "PUBLISHER") "Altium Limited"))
      (libsource (lib "Miscellaneous Devices") (part "Res3"))
    )
    (comp (ref "R52")
      (value "Res3")
      (footprint "J1-0603")
      (description "Resistor")
      (fields (field (name "ALTIUM_VALUE") "500") (field (name "PUBLISHER") "Altium Limited"))
      (libsource (lib "Miscellaneous Devices") (part "Res3"))
    )
    (comp (ref "R53")
      (value "Res3")
      (footprint "J1-0603")
      (description "Resistor")
      (fields (field (name "ALTIUM_VALUE") "1K") (field (name "PUBLISHER") "Altium Limited"))
      (libsource (lib "Miscellaneous Devices") (part "Res3"))
    )
    (comp (ref "R54")
      (value "Res3")
      (footprint "J1-0603")
      (description "Resistor")
      (fields (field (name "ALTIUM_VALUE") "1K") (field (name "PUBLISHER") "Altium Limited"))
      (libsource (lib "Miscellaneous Devices") (part "Res3"))
    )
    (comp (ref "R55")
      (value "10K")
      (footprint "J1-0603")
      (description "Resistor")
      (fields (field (name "Comment") "Res3") (field (name "PUBLISHER") "Altium Limited"))
      (libsource (lib "Miscellaneous Devices") (part "Res3"))
    )
    (comp (ref "R56")
      (value "10K")
      (footprint "J1-0603")
      (description "Resistor")
      (fields (field (name "Comment") "Res3") (field (name "PUBLISHER") "Altium Limited"))
      (libsource (lib "Miscellaneous Devices") (part "Res3"))
    )
    (comp (ref "R57")
      (value "10K")
      (footprint "J1-0603")
      (description "Resistor")
      (fields (field (name "Comment") "Res3") (field (name "PUBLISHER") "Altium Limited"))
      (libsource (lib "Miscellaneous Devices") (part "Res3"))
    )
    (comp (ref "R58")
      (value "10K")
      (footprint "J1-0603")
      (description "Resistor")
      (fields (field (name "Comment") "Res3") (field (name "PUBLISHER") "Altium Limited"))
      (libsource (lib "Miscellaneous Devices") (part "Res3"))
    )
    (comp (ref "R59")
      (value "Res3")
      (footprint "J1-0603")
      (description "Resistor")
      (fields (field (name "ALTIUM_VALUE") "50") (field (name "PUBLISHER") "Altium Limited"))
      (libsource (lib "Miscellaneous Devices") (part "Res3"))
    )
    (comp (ref "R60")
      (value "Res3")
      (footprint "J1-0603")
      (description "Resistor")
      (fields (field (name "ALTIUM_VALUE") "0") (field (name "PUBLISHER") "Altium Limited"))
      (libsource (lib "Miscellaneous Devices") (part "Res3"))
    )
    (comp (ref "R61")
      (value "Res3")
      (footprint "J1-0603")
      (description "Resistor")
      (fields (field (name "ALTIUM_VALUE") "0") (field (name "PUBLISHER") "Altium Limited"))
      (libsource (lib "Miscellaneous Devices") (part "Res3"))
    )
    (comp (ref "U1")
      (value "AMS1117-ADJ")
      (footprint "SOT-223")
      (libsource (lib "AMS1117") (part "AMS1117-ADJ"))
    )
    (comp (ref "U2")
      (value "AMS1117-1.2V")
      (footprint "SOT-223")
      (libsource (lib "AMS1117") (part "AMS1117-1.2V"))
    )
    (comp (ref "U3")
      (value "AMS1117-ADJ")
      (footprint "SOT-223")
      (libsource (lib "AMS1117") (part "AMS1117-ADJ"))
    )
    (comp (ref "U4")
      (value "M25P16-VMN3PB")
      (footprint "MICT-MN-8_N")
      (description "16 Mb (x1) Automotive Serial NOR Flash Memory, 75 MHz, 2.7 to 3.6 V, 8-pin SO8 Narrow (MN), Tube")
      (fields (field (name "VOLTAGE") "2.7V-3.6V ") (field (name "MANUFACTURER") "Micron"))
      (libsource (lib "Micron Memory Serial NOR Flash") (part "M25P16-VMN3PB"))
    )
    (comp (ref "U5")
      (value "FT232RL-Reel")
      (footprint "SSOP-28_N")
      (description "USB UART Asynchronous Serial Data Transfer Chip, 28-pin SSOP, Tape and Reel")
      (fields (field (name "MANUFACTURER") "FTDI"))
      (libsource (lib "FTDI FT Series") (part "FT232RL-Reel"))
    )
    (comp (ref "U6")
      (value "BSS138")
      (footprint "SOT-23")
      (description "BSS138 SOT-23")
      (libsource (lib "BSS138") (part "BSS138"))
    )
    (comp (ref "U7")
      (value "BSS138")
      (footprint "SOT-23")
      (description "BSS138 SOT-23")
      (libsource (lib "BSS138") (part "BSS138"))
    )
    (comp (ref "U8")
      (value "BSS138")
      (footprint "SOT-23")
      (description "BSS138 SOT-23")
      (libsource (lib "BSS138") (part "BSS138"))
    )
    (comp (ref "U9")
      (value "BSS138")
      (footprint "SOT-23")
      (description "BSS138 SOT-23")
      (libsource (lib "BSS138") (part "BSS138"))
    )
    (comp (ref "U10")
      (value "EP3C25Q240C8")
      (footprint "PQFP240_N")
      (description "Cyclone III Family FPGA, 148 I/O Pins, 4 PLLs, 240-Pin PQFP, Speed Grade 8, Commercial Grade")
      (fields (field (name "PUBLISHER") "Altium Limited"))
      (libsource (lib "Altera Cyclone III") (part "EP3C25Q240C8"))
    )
    (comp (ref "U11")
      (value "M25P16-VMN3PB")
      (footprint "MICT-MN-8_N")
      (description "16 Mb (x1) Automotive Serial NOR Flash Memory, 75 MHz, 2.7 to 3.6 V, 8-pin SO8 Narrow (MN), Tube")
      (fields (field (name "VOLTAGE") "2.7V-3.6V ") (field (name "MANUFACTURER") "Micron"))
      (libsource (lib "Micron Memory Serial NOR Flash") (part "M25P16-VMN3PB"))
    )
    (comp (ref "U12")
      (value "MT48LC4M32B2TG-7")
      (footprint "MICT-TG-86_N")
      (description "128Mb PC133 SDR SDRAM, 4Mb x 32, 7ns, 3.3V, 0 to 70 degC, 86-Pin TSOP")
      (fields (field (name "VOLTAGE") "3.3V ") (field (name "MANUFACTURER") "Micron"))
      (libsource (lib "Micron Memory SDRAM") (part "MT48LC4M32B2TG-7"))
    )
    (comp (ref "Y1")
      (value "Abracon XO ASE")
      (footprint "ABRACON ASE")
      (description "SMD CMOS Crystal Oscillator")
      (libsource (lib "ABRACON ASE") (part "Abracon XO ASE"))
    )
  )
  (nets
    (net (code "1") (name "/ASDO") (class "Default")
      (node (ref "U10") (pin "12") (pinfunction "IO,_(DATA1,_ASDO)_12") (pintype "bidirectional"))
      (node (ref "U11") (pin "5") (pinfunction "DQ0_5") (pintype "input"))
    )
    (net (code "2") (name "/AUDIO_LEFT") (class "Default")
      (node (ref "C11") (pin "2") (pinfunction "2_2") (pintype "passive"))
      (node (ref "P2") (pin "15") (pinfunction "15_15") (pintype "passive"))
      (node (ref "R33") (pin "2") (pinfunction "2_2") (pintype "passive"))
    )
    (net (code "3") (name "/AUDIO_RIGHT") (class "Default")
      (node (ref "C10") (pin "2") (pinfunction "2_2") (pintype "passive"))
      (node (ref "P2") (pin "14") (pinfunction "14_14") (pintype "passive"))
      (node (ref "R29") (pin "2") (pinfunction "2_2") (pintype "passive"))
    )
    (net (code "4") (name "/CLK_50M") (class "Default")
      (node (ref "R59") (pin "2") (pinfunction "2_2") (pintype "passive"))
      (node (ref "Y1") (pin "3") (pinfunction "OUT_3") (pintype "output"))
    )
    (net (code "5") (name "/CLK_TRI") (class "Default")
      (node (ref "R60") (pin "2") (pinfunction "2_2") (pintype "passive"))
      (node (ref "R61") (pin "1") (pinfunction "1_1") (pintype "passive"))
      (node (ref "Y1") (pin "1") (pinfunction "TRI_1") (pintype "input"))
    )
    (net (code "6") (name "/CONF_DONE") (class "Default")
      (node (ref "R58") (pin "2") (pinfunction "2_2") (pintype "passive"))
      (node (ref "U10") (pin "153") (pinfunction "CONF_DONE_153") (pintype "bidirectional"))
    )
    (net (code "7") (name "/DATA0") (class "Default")
      (node (ref "R32") (pin "2") (pinfunction "2_2") (pintype "passive"))
      (node (ref "U10") (pin "24") (pinfunction "IO,_(DATA0)_24") (pintype "bidirectional"))
    )
    (net (code "8") (name "/DCLK") (class "Default")
      (node (ref "U10") (pin "23") (pinfunction "DCLK_23") (pintype "bidirectional"))
      (node (ref "U11") (pin "6") (pinfunction "C_6") (pintype "input"))
    )
    (net (code "9") (name "/DIG_B0") (class "Default")
      (node (ref "R52") (pin "1") (pinfunction "1_1") (pintype "passive"))
      (node (ref "R53") (pin "1") (pinfunction "1_1") (pintype "passive"))
      (node (ref "U10") (pin "231") (pinfunction "IO,_DIFFIO_T6p,_(DATA6),_(DQ5T)_231") (pintype "bidirectional"))
    )
    (net (code "10") (name "/DIG_B1") (class "Default")
      (node (ref "R54") (pin "1") (pinfunction "1_1") (pintype "passive"))
      (node (ref "U10") (pin "230") (pinfunction "IO,_DIFFIO_T6n_230") (pintype "bidirectional"))
    )
    (net (code "11") (name "/DIG_G0") (class "Default")
      (node (ref "R43") (pin "1") (pinfunction "1_1") (pintype "passive"))
      (node (ref "R44") (pin "1") (pinfunction "1_1") (pintype "passive"))
      (node (ref "U10") (pin "233") (pinfunction "IO,_(DATA11)_233") (pintype "bidirectional"))
    )
    (net (code "12") (name "/DIG_G1") (class "Default")
      (node (ref "R48") (pin "1") (pinfunction "1_1") (pintype "passive"))
      (node (ref "U10") (pin "232") (pinfunction "IO,_(DATA7),_(DM5T/BWS#5T)_232") (pintype "bidirectional"))
    )
    (net (code "13") (name "/DIG_HSYNC") (class "Default")
      (node (ref "R37") (pin "2") (pinfunction "2_2") (pintype "passive"))
      (node (ref "U10") (pin "224") (pinfunction "IO,_(DATA14),_(DQS3T/CQ3T#,DPCLK11)_224") (pintype "bidirectional"))
    )
    (net (code "14") (name "/DIG_R0") (class "Default")
      (node (ref "R38") (pin "1") (pinfunction "1_1") (pintype "passive"))
      (node (ref "R40") (pin "1") (pinfunction "1_1") (pintype "passive"))
      (node (ref "U10") (pin "235") (pinfunction "IO,_DIFFIO_T2p_235") (pintype "bidirectional"))
    )
    (net (code "15") (name "/DIG_R1") (class "Default")
      (node (ref "R42") (pin "1") (pinfunction "1_1") (pintype "passive"))
      (node (ref "U10") (pin "234") (pinfunction "IO,_DIFFIO_T2n_234") (pintype "bidirectional"))
    )
    (net (code "16") (name "/DIG_VSYNC") (class "Default")
      (node (ref "R34") (pin "2") (pinfunction "2_2") (pintype "passive"))
      (node (ref "U10") (pin "226") (pinfunction "IO,_(DATA5),_(DQ5T)_226") (pintype "bidirectional"))
    )
    (net (code "17") (name "/ETH_CS") (class "Default")
      (node (ref "P4") (pin "7") (pinfunction "7_7") (pintype "passive"))
      (node (ref "U10") (pin "202") (pinfunction "IO,_DIFFIO_T15n,_(PADD7),_(DQ5T)_202") (pintype "bidirectional"))
    )
    (net (code "18") (name "/ETH_INT") (class "Default")
      (node (ref "P4") (pin "2") (pinfunction "2_2") (pintype "passive"))
      (node (ref "U10") (pin "217") (pinfunction "IO,_(DQ5T)_217") (pintype "bidirectional"))
    )
    (net (code "19") (name "/ETH_RESET") (class "Default")
      (node (ref "P4") (pin "8") (pinfunction "8_8") (pintype "passive"))
      (node (ref "U10") (pin "203") (pinfunction "IO,_DIFFIO_T15p,_(PADD8)_203") (pintype "bidirectional"))
    )
    (net (code "20") (name "/ETH_SCK") (class "Default")
      (node (ref "P4") (pin "6") (pinfunction "6_6") (pintype "passive"))
      (node (ref "U10") (pin "214") (pinfunction "IO,_(PADD17),_(DQS5T/CQ5T#,DPCLK10)_214") (pintype "bidirectional"))
    )
    (net (code "21") (name "/ETH_SI") (class "Default")
      (node (ref "P4") (pin "5") (pinfunction "5_5") (pintype "passive"))
      (node (ref "U10") (pin "207") (pinfunction "IO,_(PADD12),_(DQS4T/CQ5T,DPCLK9)_207") (pintype "bidirectional"))
    )
    (net (code "22") (name "/ETH_SO") (class "Default")
      (node (ref "P4") (pin "4") (pinfunction "4_4") (pintype "passive"))
      (node (ref "U10") (pin "216") (pinfunction "IO_216") (pintype "bidirectional"))
    )
    (net (code "23") (name "/FLASH_DQ1") (class "Default")
      (node (ref "R32") (pin "1") (pinfunction "1_1") (pintype "passive"))
      (node (ref "U11") (pin "2") (pinfunction "DQ1_2") (pintype "tri_state"))
    )
    (net (code "24") (name "/FPGA_FT232_RX") (class "Default")
      (node (ref "U10") (pin "145") (pinfunction "IO,_DIFFIO_R9p,_(DEV_CLRn)_145") (pintype "bidirectional"))
      (node (ref "U5") (pin "1") (pinfunction "TXD_1") (pintype "output"))
    )
    (net (code "25") (name "/FPGA_FT232_TX") (class "Default")
      (node (ref "U10") (pin "146") (pinfunction "IO_146") (pintype "bidirectional"))
      (node (ref "U5") (pin "5") (pinfunction "RXD_5") (pintype "input"))
    )
    (net (code "26") (name "/FPGA_KBD_CLOCK") (class "Default")
      (node (ref "D6") (pin "3") (pintype "passive"))
      (node (ref "R10") (pin "2") (pinfunction "2_2") (pintype "passive"))
      (node (ref "R17") (pin "1") (pinfunction "1_1") (pintype "passive"))
      (node (ref "U10") (pin "223") (pinfunction "IO,_VREFB8N0_223") (pintype "bidirectional"))
      (node (ref "U7") (pin "2") (pinfunction "S_2") (pintype "passive"))
    )
    (net (code "27") (name "/FPGA_KBD_DATA") (class "Default")
      (node (ref "D5") (pin "3") (pintype "passive"))
      (node (ref "R15") (pin "1") (pinfunction "1_1") (pintype "passive"))
      (node (ref "R9") (pin "2") (pinfunction "2_2") (pintype "passive"))
      (node (ref "U10") (pin "221") (pinfunction "IO,_(DATA4),_(DQ5T)_221") (pintype "bidirectional"))
      (node (ref "U6") (pin "2") (pinfunction "S_2") (pintype "passive"))
    )
    (net (code "28") (name "/FPGA_MOUSE_CLOCK") (class "Default")
      (node (ref "D8") (pin "3") (pintype "passive"))
      (node (ref "R12") (pin "2") (pinfunction "2_2") (pintype "passive"))
      (node (ref "R22") (pin "1") (pinfunction "1_1") (pintype "passive"))
      (node (ref "U10") (pin "219") (pinfunction "IO,_DIFFIO_T10p,_(DATA3),_(DQ5T)_219") (pintype "bidirectional"))
      (node (ref "U9") (pin "2") (pinfunction "S_2") (pintype "passive"))
    )
    (net (code "29") (name "/FPGA_MOUSE_DATA") (class "Default")
      (node (ref "D7") (pin "3") (pintype "passive"))
      (node (ref "R11") (pin "2") (pinfunction "2_2") (pintype "passive"))
      (node (ref "R19") (pin "1") (pinfunction "1_1") (pintype "passive"))
      (node (ref "U10") (pin "218") (pinfunction "IO,_DIFFIO_T10n,_(DATA2)_218") (pintype "bidirectional"))
      (node (ref "U8") (pin "2") (pinfunction "S_2") (pintype "passive"))
    )
    (net (code "30") (name "/FPGA_TCK") (class "Default")
      (node (ref "R36") (pin "2") (pinfunction "2_2") (pintype "passive"))
      (node (ref "U10") (pin "27") (pinfunction "TCK_27") (pintype "input"))
    )
    (net (code "31") (name "/FPGA_TDI") (class "Default")
      (node (ref "R35") (pin "2") (pinfunction "2_2") (pintype "passive"))
      (node (ref "U10") (pin "26") (pinfunction "TDI_26") (pintype "input"))
    )
    (net (code "32") (name "/GPIO0_0") (class "Default")
      (node (ref "P2") (pin "12") (pinfunction "12_12") (pintype "passive"))
      (node (ref "U10") (pin "159") (pinfunction "IO,_DIFFIO_R5n,_(INIT_DONE)_159") (pintype "bidirectional"))
    )
    (net (code "33") (name "/GPIO0_1") (class "Default")
      (node (ref "P2") (pin "11") (pinfunction "11_11") (pintype "passive"))
      (node (ref "U10") (pin "160") (pinfunction "IO,_DIFFIO_R5p,_(CRC_ERROR)_160") (pintype "bidirectional"))
    )
    (net (code "34") (name "/GPIO0_2") (class "Default")
      (node (ref "P2") (pin "10") (pinfunction "10_10") (pintype "passive"))
      (node (ref "U10") (pin "161") (pinfunction "IO_161") (pintype "bidirectional"))
    )
    (net (code "35") (name "/GPIO0_3") (class "Default")
      (node (ref "P2") (pin "9") (pinfunction "9_9") (pintype "passive"))
      (node (ref "U10") (pin "162") (pinfunction "IO,_DIFFIO_R4n,_(nCEO)_162") (pintype "bidirectional"))
    )
    (net (code "36") (name "/GPIO0_4") (class "Default")
      (node (ref "P2") (pin "8") (pinfunction "8_8") (pintype "passive"))
      (node (ref "U10") (pin "164") (pinfunction "IO,_DIFFIO_R4p,_(CLKUSR)_164") (pintype "bidirectional"))
    )
    (net (code "37") (name "/GPIO0_5") (class "Default")
      (node (ref "P2") (pin "7") (pinfunction "7_7") (pintype "passive"))
      (node (ref "U10") (pin "166") (pinfunction "IO,_(DQS0R/CQ1R,DPCLK7)_166") (pintype "bidirectional"))
    )
    (net (code "38") (name "/GPIO0_6") (class "Default")
      (node (ref "P2") (pin "6") (pinfunction "6_6") (pintype "passive"))
      (node (ref "U10") (pin "167") (pinfunction "IO,_DIFFIO_R3n,_(nWE)_167") (pintype "bidirectional"))
    )
    (net (code "39") (name "/GPIO0_7") (class "Default")
      (node (ref "P2") (pin "5") (pinfunction "5_5") (pintype "passive"))
      (node (ref "U10") (pin "168") (pinfunction "IO,_DIFFIO_R3p,_(nOE)_168") (pintype "bidirectional"))
    )
    (net (code "40") (name "/GPIO0_8") (class "Default")
      (node (ref "P2") (pin "4") (pinfunction "4_4") (pintype "passive"))
      (node (ref "U10") (pin "171") (pinfunction "IO,_(RDY),_(DQ1R)_171") (pintype "bidirectional"))
    )
    (net (code "41") (name "/GPIO0_9") (class "Default")
      (node (ref "P2") (pin "3") (pinfunction "3_3") (pintype "passive"))
      (node (ref "U10") (pin "173") (pinfunction "IO,_(PADD23)_173") (pintype "bidirectional"))
    )
    (net (code "42") (name "/GPIO0_10") (class "Default")
      (node (ref "P2") (pin "2") (pinfunction "2_2") (pintype "passive"))
      (node (ref "U10") (pin "176") (pinfunction "IO,_DIFFIO_R1n,_(PADD20),_(DQS2R/CQ3R,CDPCLK5)_176") (pintype "bidirectional"))
    )
    (net (code "43") (name "/GPIO0_11") (class "Default")
      (node (ref "P2") (pin "1") (pinfunction "1_1") (pintype "passive"))
      (node (ref "U10") (pin "177") (pinfunction "IO,_DIFFIO_R1p_177") (pintype "bidirectional"))
    )
    (net (code "44") (name "/JTAG_TCK") (class "Default")
      (node (ref "J5") (pin "1") (pinfunction "1_1") (pintype "passive"))
      (node (ref "R36") (pin "1") (pinfunction "1_1") (pintype "passive"))
    )
    (net (code "45") (name "/JTAG_TDI") (class "Default")
      (node (ref "J5") (pin "9") (pinfunction "9_9") (pintype "passive"))
      (node (ref "R35") (pin "1") (pinfunction "1_1") (pintype "passive"))
    )
    (net (code "46") (name "/JTAG_TDO") (class "Default")
      (node (ref "J5") (pin "3") (pinfunction "3_3") (pintype "passive"))
      (node (ref "U10") (pin "29") (pinfunction "TDO_29") (pintype "output"))
    )
    (net (code "47") (name "/JTAG_TMS") (class "Default")
      (node (ref "J5") (pin "5") (pinfunction "5_5") (pintype "passive"))
      (node (ref "U10") (pin "28") (pinfunction "TMS_28") (pintype "input"))
    )
    (net (code "48") (name "/KBD_CLOCK") (class "Default")
      (node (ref "J3") (pin "5") (pinfunction "PS/2_Clock_5") (pintype "bidirectional"))
      (node (ref "R10") (pin "1") (pinfunction "1_1") (pintype "passive"))
      (node (ref "R18") (pin "1") (pinfunction "1_1") (pintype "passive"))
      (node (ref "U7") (pin "3") (pinfunction "D_3") (pintype "passive"))
    )
    (net (code "49") (name "/KBD_DATA") (class "Default")
      (node (ref "J3") (pin "1") (pinfunction "PS/2_Data_1") (pintype "bidirectional"))
      (node (ref "R16") (pin "1") (pinfunction "1_1") (pintype "passive"))
      (node (ref "R9") (pin "1") (pinfunction "1_1") (pintype "passive"))
      (node (ref "U6") (pin "3") (pinfunction "D_3") (pintype "passive"))
    )
    (net (code "50") (name "/LED0") (class "Default")
      (node (ref "D9") (pin "1") (pinfunction "A_1") (pintype "passive"))
      (node (ref "U10") (pin "237") (pinfunction "IO,_DIFFIO_T1n_237") (pintype "bidirectional"))
    )
    (net (code "51") (name "/LED1") (class "Default")
      (node (ref "D10") (pin "1") (pinfunction "A_1") (pintype "passive"))
      (node (ref "U10") (pin "236") (pinfunction "IO,_(DATA12),_(DQS1T/CQ1T#,CDPCLK7)_236") (pintype "bidirectional"))
    )
    (net (code "52") (name "/MICROSD_CLK") (class "Default")
      (node (ref "J4") (pin "5") (pinfunction "5_5") (pintype "bidirectional"))
      (node (ref "U10") (pin "139") (pinfunction "IO,_DIFFIO_R11p_139") (pintype "bidirectional"))
    )
    (net (code "53") (name "/MICROSD_CMD") (class "Default")
      (node (ref "J4") (pin "3") (pinfunction "3_3") (pintype "bidirectional"))
      (node (ref "U10") (pin "142") (pinfunction "IO,_DIFFIO_R10n_142") (pintype "bidirectional"))
    )
    (net (code "54") (name "/MICROSD_DAT0") (class "Default")
      (node (ref "J4") (pin "7") (pinfunction "7_7") (pintype "bidirectional"))
      (node (ref "U10") (pin "137") (pinfunction "IO,_DIFFIO_R11n,_(DQ1R)_137") (pintype "bidirectional"))
    )
    (net (code "55") (name "/MICROSD_DAT1") (class "Default")
      (node (ref "J4") (pin "8") (pinfunction "8_8") (pintype "bidirectional"))
      (node (ref "U10") (pin "135") (pinfunction "IO,_DIFFIO_R12p,_(DQ1R)_135") (pintype "bidirectional"))
    )
    (net (code "56") (name "/MICROSD_DAT2") (class "Default")
      (node (ref "J4") (pin "1") (pinfunction "1_1") (pintype "bidirectional"))
      (node (ref "U10") (pin "144") (pinfunction "IO,_DIFFIO_R9n,_(DEV_OE)_144") (pintype "bidirectional"))
    )
    (net (code "57") (name "/MICROSD_DAT3") (class "Default")
      (node (ref "J4") (pin "2") (pinfunction "2_2") (pintype "bidirectional"))
      (node (ref "U10") (pin "143") (pinfunction "IO,_DIFFIO_R10p,_(DQS1R/CQ1R#,DPCLK6)_143") (pintype "bidirectional"))
    )
    (net (code "58") (name "/MOUSE_CLOCK") (class "Default")
      (node (ref "J1") (pin "5") (pinfunction "PS/2_Clock_5") (pintype "bidirectional"))
      (node (ref "R12") (pin "1") (pinfunction "1_1") (pintype "passive"))
      (node (ref "R23") (pin "1") (pinfunction "1_1") (pintype "passive"))
      (node (ref "U9") (pin "3") (pinfunction "D_3") (pintype "passive"))
    )
    (net (code "59") (name "/MOUSE_DATA") (class "Default")
      (node (ref "J1") (pin "1") (pinfunction "PS/2_Data_1") (pintype "bidirectional"))
      (node (ref "R11") (pin "1") (pinfunction "1_1") (pintype "passive"))
      (node (ref "R20") (pin "1") (pinfunction "1_1") (pintype "passive"))
      (node (ref "U8") (pin "3") (pinfunction "D_3") (pintype "passive"))
    )
    (net (code "60") (name "/MSEL0") (class "Default")
      (node (ref "R45") (pin "1") (pinfunction "1_1") (pintype "passive"))
      (node (ref "R49") (pin "2") (pinfunction "2_2") (pintype "passive"))
      (node (ref "U10") (pin "155") (pinfunction "MSEL0_155") (pintype "input"))
    )
    (net (code "61") (name "/MSEL1") (class "Default")
      (node (ref "R46") (pin "1") (pinfunction "1_1") (pintype "passive"))
      (node (ref "R50") (pin "2") (pinfunction "2_2") (pintype "passive"))
      (node (ref "U10") (pin "157") (pinfunction "MSEL1_157") (pintype "input"))
    )
    (net (code "62") (name "/MSEL2") (class "Default")
      (node (ref "R47") (pin "1") (pinfunction "1_1") (pintype "passive"))
      (node (ref "R51") (pin "2") (pinfunction "2_2") (pintype "passive"))
      (node (ref "U10") (pin "158") (pinfunction "MSEL2_158") (pintype "input"))
    )
    (net (code "63") (name "/PWM_LEFT") (class "Default")
      (node (ref "R33") (pin "1") (pinfunction "1_1") (pintype "passive"))
      (node (ref "U10") (pin "148") (pinfunction "IO,_DIFFIO_R7p_148") (pintype "bidirectional"))
    )
    (net (code "64") (name "/PWM_RIGHT") (class "Default")
      (node (ref "R29") (pin "1") (pinfunction "1_1") (pintype "passive"))
      (node (ref "U10") (pin "147") (pinfunction "IO,_DIFFIO_R7n_147") (pintype "bidirectional"))
    )
    (net (code "65") (name "/SDRAM_A0") (class "Default")
      (node (ref "U10") (pin "113") (pinfunction "IO,_(DQS0B/CQ1B,CDPCLK3)_113") (pintype "bidirectional"))
      (node (ref "U12") (pin "25") (pinfunction "A0_25") (pintype "input"))
    )
    (net (code "66") (name "/SDRAM_A1") (class "Default")
      (node (ref "U10") (pin "114") (pinfunction "IO_114") (pintype "bidirectional"))
      (node (ref "U12") (pin "26") (pinfunction "A1_26") (pintype "input"))
    )
    (net (code "67") (name "/SDRAM_A2") (class "Default")
      (node (ref "U10") (pin "117") (pinfunction "IO,_PLL4_CLKOUTp_117") (pintype "bidirectional"))
      (node (ref "U12") (pin "27") (pinfunction "A2_27") (pintype "input"))
    )
    (net (code "68") (name "/SDRAM_A3") (class "Default")
      (node (ref "U10") (pin "93") (pinfunction "IO,_DIFFIO_B13p,_(DQ5B)_93") (pintype "bidirectional"))
      (node (ref "U12") (pin "60") (pinfunction "A3_60") (pintype "input"))
    )
    (net (code "69") (name "/SDRAM_A4") (class "Default")
      (node (ref "U10") (pin "88") (pinfunction "IO,_(DQ5B)_88") (pintype "bidirectional"))
      (node (ref "U12") (pin "61") (pinfunction "A4_61") (pintype "input"))
    )
    (net (code "70") (name "/SDRAM_A5") (class "Default")
      (node (ref "U10") (pin "87") (pinfunction "IO,_(DQ5B)_87") (pintype "bidirectional"))
      (node (ref "U12") (pin "62") (pinfunction "A5_62") (pintype "input"))
    )
    (net (code "71") (name "/SDRAM_A6") (class "Default")
      (node (ref "U10") (pin "84") (pinfunction "IO_84") (pintype "bidirectional"))
      (node (ref "U12") (pin "63") (pinfunction "A6_63") (pintype "input"))
    )
    (net (code "72") (name "/SDRAM_A7") (class "Default")
      (node (ref "U10") (pin "83") (pinfunction "IO,_(DQS5B/CQ5B#,DPCLK3)_83") (pintype "bidirectional"))
      (node (ref "U12") (pin "64") (pinfunction "A7_64") (pintype "input"))
    )
    (net (code "73") (name "/SDRAM_A8") (class "Default")
      (node (ref "U10") (pin "82") (pinfunction "IO,_DIFFIO_B7n,_(DQ5B)_82") (pintype "bidirectional"))
      (node (ref "U12") (pin "65") (pinfunction "A8_65") (pintype "input"))
    )
    (net (code "74") (name "/SDRAM_A9") (class "Default")
      (node (ref "U10") (pin "81") (pinfunction "IO,_DIFFIO_B7p,_(DQ5B)_81") (pintype "bidirectional"))
      (node (ref "U12") (pin "66") (pinfunction "A9_66") (pintype "input"))
    )
    (net (code "75") (name "/SDRAM_A10") (class "Default")
      (node (ref "U10") (pin "112") (pinfunction "IO,_RDN2_112") (pintype "bidirectional"))
      (node (ref "U12") (pin "24") (pinfunction "A10_24") (pintype "input"))
    )
    (net (code "76") (name "/SDRAM_A11") (class "Default")
      (node (ref "U10") (pin "57") (pinfunction "IO,_DIFFIO_L15n,_(DQ1L)_57") (pintype "bidirectional"))
      (node (ref "U12") (pin "21") (pinfunction "A11_21") (pintype "input"))
    )
    (net (code "77") (name "/SDRAM_BA0") (class "Default")
      (node (ref "U10") (pin "110") (pinfunction "IO_110") (pintype "bidirectional"))
      (node (ref "U12") (pin "22") (pinfunction "BA0_22") (pintype "input"))
    )
    (net (code "78") (name "/SDRAM_BA1") (class "Default")
      (node (ref "U10") (pin "111") (pinfunction "IO,_RUP2_111") (pintype "bidirectional"))
      (node (ref "U12") (pin "23") (pinfunction "BA1_23") (pintype "input"))
    )
    (net (code "79") (name "/SDRAM_CKE") (class "Default")
      (node (ref "U10") (pin "80") (pinfunction "IO,_(DM5B/BWS#5B)_80") (pintype "bidirectional"))
      (node (ref "U12") (pin "67") (pinfunction "CKE_67") (pintype "input"))
    )
    (net (code "80") (name "/SDRAM_CLK") (class "Default")
      (node (ref "U10") (pin "78") (pinfunction "IO,_(DQS3B/CQ3B#,DPCLK2)_78") (pintype "bidirectional"))
      (node (ref "U12") (pin "68") (pinfunction "CLK_68") (pintype "input"))
    )
    (net (code "81") (name "/SDRAM_DQ0") (class "Default")
      (node (ref "U10") (pin "37") (pinfunction "IO,_DIFFIO_L8p,_(DQ1L)_37") (pintype "bidirectional"))
      (node (ref "U12") (pin "2") (pinfunction "DQ0_2") (pintype "bidirectional"))
    )
    (net (code "82") (name "/SDRAM_DQ1") (class "Default")
      (node (ref "U10") (pin "38") (pinfunction "IO,_DIFFIO_L8n,_(DQ1L)_38") (pintype "bidirectional"))
      (node (ref "U12") (pin "4") (pinfunction "DQ1_4") (pintype "bidirectional"))
    )
    (net (code "83") (name "/SDRAM_DQ2") (class "Default")
      (node (ref "U10") (pin "39") (pinfunction "IO_39") (pintype "bidirectional"))
      (node (ref "U12") (pin "5") (pinfunction "DQ2_5") (pintype "bidirectional"))
    )
    (net (code "84") (name "/SDRAM_DQ3") (class "Default")
      (node (ref "U10") (pin "41") (pinfunction "IO,_DIFFIO_L10p,_(DQ1L)_41") (pintype "bidirectional"))
      (node (ref "U12") (pin "7") (pinfunction "DQ3_7") (pintype "bidirectional"))
    )
    (net (code "85") (name "/SDRAM_DQ4") (class "Default")
      (node (ref "U10") (pin "43") (pinfunction "IO,_DIFFIO_L10n,_(DQ1L)_43") (pintype "bidirectional"))
      (node (ref "U12") (pin "8") (pinfunction "DQ4_8") (pintype "bidirectional"))
    )
    (net (code "86") (name "/SDRAM_DQ5") (class "Default")
      (node (ref "U10") (pin "44") (pinfunction "IO,_DIFFIO_L11p,_(DQS1L/CQ1L#,DPCLK1)_44") (pintype "bidirectional"))
      (node (ref "U12") (pin "10") (pinfunction "DQ5_10") (pintype "bidirectional"))
    )
    (net (code "87") (name "/SDRAM_DQ6") (class "Default")
      (node (ref "U10") (pin "45") (pinfunction "IO,_DIFFIO_L11n,_(DQ1L)_45") (pintype "bidirectional"))
      (node (ref "U12") (pin "11") (pinfunction "DQ6_11") (pintype "bidirectional"))
    )
    (net (code "88") (name "/SDRAM_DQ7") (class "Default")
      (node (ref "U10") (pin "49") (pinfunction "IO,_DIFFIO_L13p,_(DQ1L)_49") (pintype "bidirectional"))
      (node (ref "U12") (pin "13") (pinfunction "DQ7_13") (pintype "bidirectional"))
    )
    (net (code "89") (name "/SDRAM_DQ8") (class "Default")
      (node (ref "U10") (pin "72") (pinfunction "IO,_DIFFIO_B4n_72") (pintype "bidirectional"))
      (node (ref "U12") (pin "74") (pinfunction "DQ8_74") (pintype "bidirectional"))
    )
    (net (code "90") (name "/SDRAM_DQ9") (class "Default")
      (node (ref "U10") (pin "71") (pinfunction "IO,_DIFFIO_B4p_71") (pintype "bidirectional"))
      (node (ref "U12") (pin "76") (pinfunction "DQ9_76") (pintype "bidirectional"))
    )
    (net (code "91") (name "/SDRAM_DQ10") (class "Default")
      (node (ref "U10") (pin "70") (pinfunction "IO,_PLL1_CLKOUTn_70") (pintype "bidirectional"))
      (node (ref "U12") (pin "77") (pinfunction "DQ10_77") (pintype "bidirectional"))
    )
    (net (code "92") (name "/SDRAM_DQ11") (class "Default")
      (node (ref "U10") (pin "69") (pinfunction "IO,_PLL1_CLKOUTp_69") (pintype "bidirectional"))
      (node (ref "U12") (pin "79") (pinfunction "DQ11_79") (pintype "bidirectional"))
    )
    (net (code "93") (name "/SDRAM_DQ12") (class "Default")
      (node (ref "U10") (pin "68") (pinfunction "IO,_(DQS1B/CQ1B#,CDPCLK2)_68") (pintype "bidirectional"))
      (node (ref "U12") (pin "80") (pinfunction "DQ12_80") (pintype "bidirectional"))
    )
    (net (code "94") (name "/SDRAM_DQ13") (class "Default")
      (node (ref "U10") (pin "65") (pinfunction "IO_65") (pintype "bidirectional"))
      (node (ref "U12") (pin "82") (pinfunction "DQ13_82") (pintype "bidirectional"))
    )
    (net (code "95") (name "/SDRAM_DQ14") (class "Default")
      (node (ref "U10") (pin "64") (pinfunction "IO,_DIFFIO_B2n_64") (pintype "bidirectional"))
      (node (ref "U12") (pin "83") (pinfunction "DQ14_83") (pintype "bidirectional"))
    )
    (net (code "96") (name "/SDRAM_DQ15") (class "Default")
      (node (ref "U10") (pin "63") (pinfunction "IO,_DIFFIO_B2p_63") (pintype "bidirectional"))
      (node (ref "U12") (pin "85") (pinfunction "DQ15_85") (pintype "bidirectional"))
    )
    (net (code "97") (name "/SDRAM_DQ16") (class "Default")
      (node (ref "U10") (pin "119") (pinfunction "IO,_DIFFIO_B25p_119") (pintype "bidirectional"))
      (node (ref "U12") (pin "31") (pinfunction "DQ16_31") (pintype "bidirectional"))
    )
    (net (code "98") (name "/SDRAM_DQ17") (class "Default")
      (node (ref "U10") (pin "120") (pinfunction "IO,_DIFFIO_B25n_120") (pintype "bidirectional"))
      (node (ref "U12") (pin "33") (pinfunction "DQ17_33") (pintype "bidirectional"))
    )
    (net (code "99") (name "/SDRAM_DQ18") (class "Default")
      (node (ref "U10") (pin "126") (pinfunction "IO,_RUP3,_(DQ1R)_126") (pintype "bidirectional"))
      (node (ref "U12") (pin "34") (pinfunction "DQ18_34") (pintype "bidirectional"))
    )
    (net (code "100") (name "/SDRAM_DQ19") (class "Default")
      (node (ref "U10") (pin "127") (pinfunction "IO,_RDN3,_(DQ1R)_127") (pintype "bidirectional"))
      (node (ref "U12") (pin "36") (pinfunction "DQ19_36") (pintype "bidirectional"))
    )
    (net (code "101") (name "/SDRAM_DQ20") (class "Default")
      (node (ref "U10") (pin "128") (pinfunction "IO,_(DQS3R/CQ3R#,CDPCLK4)_128") (pintype "bidirectional"))
      (node (ref "U12") (pin "37") (pinfunction "DQ20_37") (pintype "bidirectional"))
    )
    (net (code "102") (name "/SDRAM_DQ21") (class "Default")
      (node (ref "U10") (pin "131") (pinfunction "IO,_DIFFIO_R13n,_(DQ1R)_131") (pintype "bidirectional"))
      (node (ref "U12") (pin "39") (pinfunction "DQ21_39") (pintype "bidirectional"))
    )
    (net (code "103") (name "/SDRAM_DQ22") (class "Default")
      (node (ref "U10") (pin "132") (pinfunction "IO,_DIFFIO_R13p,_(DQ1R)_132") (pintype "bidirectional"))
      (node (ref "U12") (pin "40") (pinfunction "DQ22_40") (pintype "bidirectional"))
    )
    (net (code "104") (name "/SDRAM_DQ23") (class "Default")
      (node (ref "U10") (pin "134") (pinfunction "IO,_DIFFIO_R12n,_(DQ1R)_134") (pintype "bidirectional"))
      (node (ref "U12") (pin "42") (pinfunction "DQ23_42") (pintype "bidirectional"))
    )
    (net (code "105") (name "/SDRAM_DQ24") (class "Default")
      (node (ref "U10") (pin "109") (pinfunction "IO,_DIFFIO_B20n_109") (pintype "bidirectional"))
      (node (ref "U12") (pin "45") (pinfunction "DQ24_45") (pintype "bidirectional"))
    )
    (net (code "106") (name "/SDRAM_DQ25") (class "Default")
      (node (ref "U10") (pin "108") (pinfunction "IO,_DIFFIO_B20p_108") (pintype "bidirectional"))
      (node (ref "U12") (pin "47") (pinfunction "DQ25_47") (pintype "bidirectional"))
    )
    (net (code "107") (name "/SDRAM_DQ26") (class "Default")
      (node (ref "U10") (pin "106") (pinfunction "IO,_(DQS2B/CQ3B,DPCLK5)_106") (pintype "bidirectional"))
      (node (ref "U12") (pin "48") (pinfunction "DQ26_48") (pintype "bidirectional"))
    )
    (net (code "108") (name "/SDRAM_DQ27") (class "Default")
      (node (ref "U10") (pin "103") (pinfunction "IO,_(DQ5B)_103") (pintype "bidirectional"))
      (node (ref "U12") (pin "50") (pinfunction "DQ27_50") (pintype "bidirectional"))
    )
    (net (code "109") (name "/SDRAM_DQ28") (class "Default")
      (node (ref "U10") (pin "100") (pinfunction "IO,_(DQ5B)_100") (pintype "bidirectional"))
      (node (ref "U12") (pin "51") (pinfunction "DQ28_51") (pintype "bidirectional"))
    )
    (net (code "110") (name "/SDRAM_DQ29") (class "Default")
      (node (ref "U10") (pin "99") (pinfunction "IO,_DIFFIO_B16n,_(DQS4B/CQ5B,DPCLK4)_99") (pintype "bidirectional"))
      (node (ref "U12") (pin "53") (pinfunction "DQ29_53") (pintype "bidirectional"))
    )
    (net (code "111") (name "/SDRAM_DQ30") (class "Default")
      (node (ref "U10") (pin "98") (pinfunction "IO,_DIFFIO_B16p,_(DQ5B)_98") (pintype "bidirectional"))
      (node (ref "U12") (pin "54") (pinfunction "DQ30_54") (pintype "bidirectional"))
    )
    (net (code "112") (name "/SDRAM_DQ31") (class "Default")
      (node (ref "U10") (pin "95") (pinfunction "IO_95") (pintype "bidirectional"))
      (node (ref "U12") (pin "56") (pinfunction "DQ31_56") (pintype "bidirectional"))
    )
    (net (code "113") (name "/SDRAM_DQM0") (class "Default")
      (node (ref "U10") (pin "50") (pinfunction "IO,_DIFFIO_L13n_50") (pintype "bidirectional"))
      (node (ref "U12") (pin "16") (pinfunction "DQM0_16") (pintype "input"))
    )
    (net (code "114") (name "/SDRAM_DQM1") (class "Default")
      (node (ref "U10") (pin "73") (pinfunction "IO_73") (pintype "bidirectional"))
      (node (ref "U12") (pin "71") (pinfunction "DQM1_71") (pintype "input"))
    )
    (net (code "115") (name "/SDRAM_DQM2") (class "Default")
      (node (ref "U10") (pin "118") (pinfunction "IO,_PLL4_CLKOUTn_118") (pintype "bidirectional"))
      (node (ref "U12") (pin "28") (pinfunction "DQM2_28") (pintype "input"))
    )
    (net (code "116") (name "/SDRAM_DQM3") (class "Default")
      (node (ref "U10") (pin "94") (pinfunction "IO,_DIFFIO_B13n,_(DQ5B)_94") (pintype "bidirectional"))
      (node (ref "U12") (pin "59") (pinfunction "DQM3_59") (pintype "input"))
    )
    (net (code "117") (name "/SDRAM_nCAS") (class "Default")
      (node (ref "U10") (pin "52") (pinfunction "IO,_RDN1,_(DQ1L)_52") (pintype "bidirectional"))
      (node (ref "U12") (pin "18") (pinfunction "CAS#_18") (pintype "input"))
    )
    (net (code "118") (name "/SDRAM_nCS") (class "Default")
      (node (ref "U10") (pin "56") (pinfunction "IO,_DIFFIO_L15p_56") (pintype "bidirectional"))
      (node (ref "U12") (pin "20") (pinfunction "CS#_20") (pintype "input"))
    )
    (net (code "119") (name "/SDRAM_nRAS") (class "Default")
      (node (ref "U10") (pin "55") (pinfunction "IO,_(DQS3L/CQ3L#,CDPCLK1)_55") (pintype "bidirectional"))
      (node (ref "U12") (pin "19") (pinfunction "RAS#_19") (pintype "input"))
    )
    (net (code "120") (name "/SDRAM_nWE") (class "Default")
      (node (ref "U10") (pin "51") (pinfunction "IO,_RUP1,_(DQ1L)_51") (pintype "bidirectional"))
      (node (ref "U12") (pin "17") (pinfunction "WE#_17") (pintype "input"))
    )
    (net (code "121") (name "/USBDM") (class "Default")
      (node (ref "J2") (pin "2") (pinfunction "D-_2") (pintype "passive"))
      (node (ref "U5") (pin "16") (pinfunction "USBDM_16") (pintype "bidirectional"))
    )
    (net (code "122") (name "/USBDP") (class "Default")
      (node (ref "J2") (pin "3") (pinfunction "D+_3") (pintype "passive"))
      (node (ref "U5") (pin "15") (pinfunction "USBDP_15") (pintype "bidirectional"))
    )
    (net (code "123") (name "/USER_FLASH_CLK") (class "Default")
      (node (ref "U10") (pin "239") (pinfunction "IO,_PLL3_CLKOUTn_239") (pintype "bidirectional"))
      (node (ref "U4") (pin "6") (pinfunction "C_6") (pintype "input"))
    )
    (net (code "124") (name "/USER_FLASH_CS") (class "Default")
      (node (ref "U10") (pin "6") (pinfunction "IO_6") (pintype "bidirectional"))
      (node (ref "U4") (pin "1") (pinfunction "S#_1") (pintype "input"))
    )
    (net (code "125") (name "/USER_FLASH_DQ0") (class "Default")
      (node (ref "U10") (pin "240") (pinfunction "IO,_PLL3_CLKOUTp_240") (pintype "bidirectional"))
      (node (ref "U4") (pin "5") (pinfunction "DQ0_5") (pintype "input"))
    )
    (net (code "126") (name "/USER_FLASH_DQ1") (class "Default")
      (node (ref "U10") (pin "5") (pinfunction "IO,_DIFFIO_L1n_5") (pintype "bidirectional"))
      (node (ref "U4") (pin "2") (pinfunction "DQ1_2") (pintype "tri_state"))
    )
    (net (code "127") (name "/USER_FLASH_DQ2") (class "Default")
      (node (ref "U10") (pin "4") (pinfunction "IO,_DIFFIO_L1p_4") (pintype "bidirectional"))
      (node (ref "U4") (pin "3") (pinfunction "W#_3") (pintype "input"))
    )
    (net (code "128") (name "/USER_FLASH_DQ3") (class "Default")
      (node (ref "U10") (pin "238") (pinfunction "IO,_DIFFIO_T1p_238") (pintype "bidirectional"))
      (node (ref "U4") (pin "7") (pinfunction "HOLD#_7") (pintype "input"))
    )
    (net (code "129") (name "/VGA_B") (class "Default")
      (node (ref "1") (pin "3") (pinfunction "3_3") (pintype "passive"))
      (node (ref "R52") (pin "2") (pinfunction "2_2") (pintype "passive"))
      (node (ref "R53") (pin "2") (pinfunction "2_2") (pintype "passive"))
      (node (ref "R54") (pin "2") (pinfunction "2_2") (pintype "passive"))
    )
    (net (code "130") (name "/VGA_G") (class "Default")
      (node (ref "1") (pin "2") (pinfunction "2_2") (pintype "passive"))
      (node (ref "R43") (pin "2") (pinfunction "2_2") (pintype "passive"))
      (node (ref "R44") (pin "2") (pinfunction "2_2") (pintype "passive"))
      (node (ref "R48") (pin "2") (pinfunction "2_2") (pintype "passive"))
    )
    (net (code "131") (name "/VGA_HSYNC") (class "Default")
      (node (ref "1") (pin "13") (pinfunction "13_13") (pintype "passive"))
      (node (ref "R37") (pin "1") (pinfunction "1_1") (pintype "passive"))
    )
    (net (code "132") (name "/VGA_R") (class "Default")
      (node (ref "1") (pin "1") (pinfunction "1_1") (pintype "passive"))
      (node (ref "R38") (pin "2") (pinfunction "2_2") (pintype "passive"))
      (node (ref "R40") (pin "2") (pinfunction "2_2") (pintype "passive"))
      (node (ref "R42") (pin "2") (pinfunction "2_2") (pintype "passive"))
    )
    (net (code "133") (name "/VGA_VSYNC") (class "Default")
      (node (ref "1") (pin "14") (pinfunction "14_14") (pintype "passive"))
      (node (ref "R34") (pin "1") (pinfunction "1_1") (pintype "passive"))
    )
    (net (code "134") (name "/WIFI_CH_PD") (class "Default")
      (node (ref "P3") (pin "6") (pinfunction "6_6") (pintype "passive"))
      (node (ref "R25") (pin "1") (pinfunction "1_1") (pintype "passive"))
    )
    (net (code "135") (name "/WIFI_GPIO0") (class "Default")
      (node (ref "P3") (pin "3") (pinfunction "3_3") (pintype "passive"))
      (node (ref "R28") (pin "1") (pinfunction "1_1") (pintype "passive"))
      (node (ref "R30") (pin "2") (pinfunction "2_2") (pintype "passive"))
    )
    (net (code "136") (name "/WIFI_GPIO2") (class "Default")
      (node (ref "P3") (pin "5") (pinfunction "5_5") (pintype "passive"))
      (node (ref "R27") (pin "1") (pinfunction "1_1") (pintype "passive"))
    )
    (net (code "137") (name "/WIFI_RESET") (class "Default")
      (node (ref "P3") (pin "4") (pinfunction "4_4") (pintype "passive"))
      (node (ref "R26") (pin "1") (pinfunction "1_1") (pintype "passive"))
      (node (ref "U10") (pin "200") (pinfunction "IO,_(PADD4),_(DQS2T/CQ3T,DPCLK8)_200") (pintype "bidirectional"))
    )
    (net (code "138") (name "/WIFI_RXD") (class "Default")
      (node (ref "P3") (pin "1") (pinfunction "1_1") (pintype "passive"))
      (node (ref "U10") (pin "201") (pinfunction "IO,_(PADD5),_(DQ5T)_201") (pintype "bidirectional"))
    )
    (net (code "139") (name "/WIFI_TXD") (class "Default")
      (node (ref "P3") (pin "8") (pinfunction "8_8") (pintype "passive"))
      (node (ref "U10") (pin "197") (pinfunction "IO,_DIFFIO_T19p,_(PADD2),_(DQ5T)_197") (pintype "bidirectional"))
    )
    (net (code "140") (name "/nCE") (class "Default")
      (node (ref "R55") (pin "1") (pinfunction "1_1") (pintype "passive"))
      (node (ref "U10") (pin "30") (pinfunction "nCE_30") (pintype "input"))
    )
    (net (code "141") (name "/nCONFIG") (class "Default")
      (node (ref "R56") (pin "2") (pinfunction "2_2") (pintype "passive"))
      (node (ref "U10") (pin "25") (pinfunction "nCONFIG_25") (pintype "input"))
    )
    (net (code "142") (name "/nCSO") (class "Default")
      (node (ref "U10") (pin "14") (pinfunction "IO,_(FLASH_nCE,_nCSO)_14") (pintype "bidirectional"))
      (node (ref "U11") (pin "1") (pinfunction "S#_1") (pintype "input"))
    )
    (net (code "143") (name "/nSTATUS") (class "Default")
      (node (ref "R57") (pin "2") (pinfunction "2_2") (pintype "passive"))
      (node (ref "U10") (pin "17") (pinfunction "nSTATUS_17") (pintype "bidirectional"))
    )
    (net (code "144") (name "1.2V") (class "Default")
      (node (ref "C26") (pin "2") (pinfunction "2_2") (pintype "passive"))
      (node (ref "C27") (pin "2") (pinfunction "2_2") (pintype "passive"))
      (node (ref "C28") (pin "2") (pinfunction "2_2") (pintype "passive"))
      (node (ref "C29") (pin "2") (pinfunction "2_2") (pintype "passive"))
      (node (ref "C30") (pin "2") (pinfunction "2_2") (pintype "passive"))
      (node (ref "C31") (pin "2") (pinfunction "2_2") (pintype "passive"))
      (node (ref "C32") (pin "2") (pinfunction "2_2") (pintype "passive"))
      (node (ref "C33") (pin "2") (pinfunction "2_2") (pintype "passive"))
      (node (ref "C34") (pin "2") (pinfunction "2_2") (pintype "passive"))
      (node (ref "C35") (pin "2") (pinfunction "2_2") (pintype "passive"))
      (node (ref "C36") (pin "2") (pinfunction "2_2") (pintype "passive"))
      (node (ref "C37") (pin "2") (pinfunction "2_2") (pintype "passive"))
      (node (ref "C38") (pin "2") (pinfunction "2_2") (pintype "passive"))
      (node (ref "C39") (pin "2") (pinfunction "2_2") (pintype "passive"))
      (node (ref "C4") (pin "1") (pinfunction "1_1") (pintype "passive"))
      (node (ref "C40") (pin "2") (pinfunction "2_2") (pintype "passive"))
      (node (ref "C41") (pin "2") (pinfunction "2_2") (pintype "passive"))
      (node (ref "C42") (pin "2") (pinfunction "2_2") (pintype "passive"))
      (node (ref "C67") (pin "2") (pinfunction "2_2") (pintype "passive"))
      (node (ref "C68") (pin "2") (pinfunction "2_2") (pintype "passive"))
      (node (ref "C69") (pin "2") (pinfunction "2_2") (pintype "passive"))
      (node (ref "D4") (pin "1") (pinfunction "A_1") (pintype "passive"))
      (node (ref "P1") (pin "4") (pinfunction "4_4") (pintype "passive"))
      (node (ref "U10") (pin "1") (pinfunction "VCCD_PLL3_1") (pintype "power_in"))
      (node (ref "U10") (pin "10") (pinfunction "VCCINT_10") (pintype "power_in"))
      (node (ref "U10") (pin "101") (pinfunction "VCCINT_101") (pintype "power_in"))
      (node (ref "U10") (pin "115") (pinfunction "VCCINT_115") (pintype "power_in"))
      (node (ref "U10") (pin "121") (pinfunction "VCCD_PLL4_121") (pintype "power_in"))
      (node (ref "U10") (pin "129") (pinfunction "VCCINT_129") (pintype "power_in"))
      (node (ref "U10") (pin "140") (pinfunction "VCCINT_140") (pintype "power_in"))
      (node (ref "U10") (pin "163") (pinfunction "VCCINT_163") (pintype "power_in"))
      (node (ref "U10") (pin "174") (pinfunction "VCCINT_174") (pintype "power_in"))
      (node (ref "U10") (pin "180") (pinfunction "VCCD_PLL2_180") (pintype "power_in"))
      (node (ref "U10") (pin "19") (pinfunction "VCCINT_19") (pintype "power_in"))
      (node (ref "U10") (pin "190") (pinfunction "VCCINT_190") (pintype "power_in"))
      (node (ref "U10") (pin "198") (pinfunction "VCCINT_198") (pintype "power_in"))
      (node (ref "U10") (pin "204") (pinfunction "VCCINT_204") (pintype "power_in"))
      (node (ref "U10") (pin "220") (pinfunction "VCCINT_220") (pintype "power_in"))
      (node (ref "U10") (pin "228") (pinfunction "VCCINT_228") (pintype "power_in"))
      (node (ref "U10") (pin "40") (pinfunction "VCCINT_40") (pintype "power_in"))
      (node (ref "U10") (pin "53") (pinfunction "VCCINT_53") (pintype "power_in"))
      (node (ref "U10") (pin "60") (pinfunction "VCCD_PLL1_60") (pintype "power_in"))
      (node (ref "U10") (pin "61") (pinfunction "VCCINT_61") (pintype "power_in"))
      (node (ref "U10") (pin "74") (pinfunction "VCCINT_74") (pintype "power_in"))
      (node (ref "U10") (pin "85") (pinfunction "VCCINT_85") (pintype "power_in"))
      (node (ref "U2") (pin "2") (pinfunction "Vout_2") (pintype "passive"))
    )
    (net (code "145") (name "2.5V") (class "Default")
      (node (ref "C3") (pin "1") (pinfunction "1_1") (pintype "passive"))
      (node (ref "C57") (pin "2") (pinfunction "2_2") (pintype "passive"))
      (node (ref "C58") (pin "2") (pinfunction "2_2") (pintype "passive"))
      (node (ref "C59") (pin "2") (pinfunction "2_2") (pintype "passive"))
      (node (ref "C60") (pin "2") (pinfunction "2_2") (pintype "passive"))
      (node (ref "D3") (pin "1") (pinfunction "A_1") (pintype "passive"))
      (node (ref "P1") (pin "3") (pinfunction "3_3") (pintype "passive"))
      (node (ref "R39") (pin "2") (pinfunction "2_2") (pintype "passive"))
      (node (ref "R4") (pin "2") (pinfunction "2_2") (pintype "passive"))
      (node (ref "R45") (pin "2") (pinfunction "2_2") (pintype "passive"))
      (node (ref "R46") (pin "2") (pinfunction "2_2") (pintype "passive"))
      (node (ref "R47") (pin "2") (pinfunction "2_2") (pintype "passive"))
      (node (ref "U1") (pin "2") (pinfunction "Vout_2") (pintype "passive"))
      (node (ref "U10") (pin "123") (pinfunction "VCCA4_123") (pintype "power_in"))
      (node (ref "U10") (pin "178") (pinfunction "VCCA2_178") (pintype "power_in"))
      (node (ref "U10") (pin "3") (pinfunction "VCCA3_3") (pintype "power_in"))
      (node (ref "U10") (pin "58") (pinfunction "VCCA1_58") (pintype "power_in"))
      (node (ref "U2") (pin "3") (pinfunction "Vin_3") (pintype "passive"))
    )
    (net (code "146") (name "3V") (class "Default")
      (node (ref "C13") (pin "2") (pinfunction "2_2") (pintype "passive"))
      (node (ref "C14") (pin "2") (pinfunction "2_2") (pintype "passive"))
      (node (ref "C15") (pin "2") (pinfunction "2_2") (pintype "passive"))
      (node (ref "C16") (pin "2") (pinfunction "2_2") (pintype "passive"))
      (node (ref "C17") (pin "2") (pinfunction "2_2") (pintype "passive"))
      (node (ref "C18") (pin "2") (pinfunction "2_2") (pintype "passive"))
      (node (ref "C19") (pin "2") (pinfunction "2_2") (pintype "passive"))
      (node (ref "C2") (pin "1") (pinfunction "1_1") (pintype "passive"))
      (node (ref "C20") (pin "2") (pinfunction "2_2") (pintype "passive"))
      (node (ref "C21") (pin "2") (pinfunction "2_2") (pintype "passive"))
      (node (ref "C22") (pin "2") (pinfunction "2_2") (pintype "passive"))
      (node (ref "C23") (pin "2") (pinfunction "2_2") (pintype "passive"))
      (node (ref "C24") (pin "2") (pinfunction "2_2") (pintype "passive"))
      (node (ref "C25") (pin "2") (pinfunction "2_2") (pintype "passive"))
      (node (ref "C43") (pin "2") (pinfunction "2_2") (pintype "passive"))
      (node (ref "C44") (pin "2") (pinfunction "2_2") (pintype "passive"))
      (node (ref "C45") (pin "2") (pinfunction "2_2") (pintype "passive"))
      (node (ref "C46") (pin "2") (pinfunction "2_2") (pintype "passive"))
      (node (ref "C47") (pin "2") (pinfunction "2_2") (pintype "passive"))
      (node (ref "C48") (pin "2") (pinfunction "2_2") (pintype "passive"))
      (node (ref "C49") (pin "2") (pinfunction "2_2") (pintype "passive"))
      (node (ref "C50") (pin "2") (pinfunction "2_2") (pintype "passive"))
      (node (ref "C51") (pin "2") (pinfunction "2_2") (pintype "passive"))
      (node (ref "C52") (pin "2") (pinfunction "2_2") (pintype "passive"))
      (node (ref "C53") (pin "2") (pinfunction "2_2") (pintype "passive"))
      (node (ref "C54") (pin "2") (pinfunction "2_2") (pintype "passive"))
      (node (ref "C55") (pin "2") (pinfunction "2_2") (pintype "passive"))
      (node (ref "C56") (pin "2") (pinfunction "2_2") (pintype "passive"))
      (node (ref "C6") (pin "2") (pinfunction "2_2") (pintype "passive"))
      (node (ref "C61") (pin "2") (pinfunction "2_2") (pintype "passive"))
      (node (ref "C62") (pin "2") (pinfunction "2_2") (pintype "passive"))
      (node (ref "C63") (pin "2") (pinfunction "2_2") (pintype "passive"))
      (node (ref "C64") (pin "2") (pinfunction "2_2") (pintype "passive"))
      (node (ref "C65") (pin "2") (pinfunction "2_2") (pintype "passive"))
      (node (ref "C66") (pin "2") (pinfunction "2_2") (pintype "passive"))
      (node (ref "C8") (pin "1") (pinfunction "1_1") (pintype "passive"))
      (node (ref "C9") (pin "2") (pinfunction "2_2") (pintype "passive"))
      (node (ref "D2") (pin "1") (pinfunction "A_1") (pintype "passive"))
      (node (ref "D5") (pin "2") (pintype "passive"))
      (node (ref "D6") (pin "2") (pintype "passive"))
      (node (ref "D7") (pin "2") (pintype "passive"))
      (node (ref "D8") (pin "2") (pintype "passive"))
      (node (ref "J4") (pin "4") (pinfunction "4_4") (pintype "bidirectional"))
      (node (ref "P1") (pin "2") (pinfunction "2_2") (pintype "passive"))
      (node (ref "P2") (pin "17") (pinfunction "17_17") (pintype "passive"))
      (node (ref "P3") (pin "2") (pinfunction "2_2") (pintype "passive"))
      (node (ref "P4") (pin "9") (pinfunction "9_9") (pintype "passive"))
      (node (ref "R13") (pin "2") (pinfunction "2_2") (pintype "passive"))
      (node (ref "R14") (pin "1") (pinfunction "1_1") (pintype "passive"))
      (node (ref "R15") (pin "2") (pinfunction "2_2") (pintype "passive"))
      (node (ref "R17") (pin "2") (pinfunction "2_2") (pintype "passive"))
      (node (ref "R19") (pin "2") (pinfunction "2_2") (pintype "passive"))
      (node (ref "R22") (pin "2") (pinfunction "2_2") (pintype "passive"))
      (node (ref "R25") (pin "2") (pinfunction "2_2") (pintype "passive"))
      (node (ref "R26") (pin "2") (pinfunction "2_2") (pintype "passive"))
      (node (ref "R27") (pin "2") (pinfunction "2_2") (pintype "passive"))
      (node (ref "R28") (pin "2") (pinfunction "2_2") (pintype "passive"))
      (node (ref "R31") (pin "2") (pinfunction "2_2") (pintype "passive"))
      (node (ref "R41") (pin "2") (pinfunction "2_2") (pintype "passive"))
      (node (ref "R5") (pin "2") (pinfunction "2_2") (pintype "passive"))
      (node (ref "R56") (pin "1") (pinfunction "1_1") (pintype "passive"))
      (node (ref "R57") (pin "1") (pinfunction "1_1") (pintype "passive"))
      (node (ref "R58") (pin "1") (pinfunction "1_1") (pintype "passive"))
      (node (ref "R60") (pin "1") (pinfunction "1_1") (pintype "passive"))
      (node (ref "U10") (pin "104") (pinfunction "VCCIO4_104") (pintype "power_in"))
      (node (ref "U10") (pin "124") (pinfunction "VCCIO5_124") (pintype "power_in"))
      (node (ref "U10") (pin "136") (pinfunction "VCCIO5_136") (pintype "power_in"))
      (node (ref "U10") (pin "15") (pinfunction "VCCIO1_15") (pintype "power_in"))
      (node (ref "U10") (pin "154") (pinfunction "VCCIO6_154") (pintype "power_in"))
      (node (ref "U10") (pin "170") (pinfunction "VCCIO6_170") (pintype "power_in"))
      (node (ref "U10") (pin "192") (pinfunction "VCCIO7_192") (pintype "power_in"))
      (node (ref "U10") (pin "206") (pinfunction "VCCIO7_206") (pintype "power_in"))
      (node (ref "U10") (pin "213") (pinfunction "VCCIO8_213") (pintype "power_in"))
      (node (ref "U10") (pin "225") (pinfunction "VCCIO8_225") (pintype "power_in"))
      (node (ref "U10") (pin "35") (pinfunction "VCCIO2_35") (pintype "power_in"))
      (node (ref "U10") (pin "47") (pinfunction "VCCIO2_47") (pintype "power_in"))
      (node (ref "U10") (pin "66") (pinfunction "VCCIO3_66") (pintype "power_in"))
      (node (ref "U10") (pin "7") (pinfunction "VCCIO1_7") (pintype "power_in"))
      (node (ref "U10") (pin "77") (pinfunction "VCCIO3_77") (pintype "power_in"))
      (node (ref "U10") (pin "96") (pinfunction "VCCIO4_96") (pintype "power_in"))
      (node (ref "U11") (pin "8") (pinfunction "VCC_8") (pintype "power_in"))
      (node (ref "U12") (pin "1") (pinfunction "VDD_1") (pintype "power_in"))
      (node (ref "U12") (pin "15") (pinfunction "VDD_15") (pintype "power_in"))
      (node (ref "U12") (pin "29") (pinfunction "VDD_29") (pintype "power_in"))
      (node (ref "U12") (pin "3") (pinfunction "VDDQ_3") (pintype "power_in"))
      (node (ref "U12") (pin "35") (pinfunction "VDDQ_35") (pintype "power_in"))
      (node (ref "U12") (pin "41") (pinfunction "VDDQ_41") (pintype "power_in"))
      (node (ref "U12") (pin "43") (pinfunction "VDD_43") (pintype "power_in"))
      (node (ref "U12") (pin "49") (pinfunction "VDDQ_49") (pintype "power_in"))
      (node (ref "U12") (pin "55") (pinfunction "VDDQ_55") (pintype "power_in"))
      (node (ref "U12") (pin "75") (pinfunction "VDDQ_75") (pintype "power_in"))
      (node (ref "U12") (pin "81") (pinfunction "VDDQ_81") (pintype "power_in"))
      (node (ref "U12") (pin "9") (pinfunction "VDDQ_9") (pintype "power_in"))
      (node (ref "U3") (pin "2") (pinfunction "Vout_2") (pintype "passive"))
      (node (ref "U4") (pin "8") (pinfunction "VCC_8") (pintype "power_in"))
      (node (ref "U5") (pin "4") (pinfunction "VCCIO_4") (pintype "power_in"))
      (node (ref "U6") (pin "1") (pinfunction "G_1") (pintype "passive"))
      (node (ref "U7") (pin "1") (pinfunction "G_1") (pintype "passive"))
      (node (ref "U8") (pin "1") (pinfunction "G_1") (pintype "passive"))
      (node (ref "U9") (pin "1") (pinfunction "G_1") (pintype "passive"))
      (node (ref "Y1") (pin "4") (pinfunction "VDD_4") (pintype "power_in"))
    )
    (net (code "147") (name "5V") (class "Default")
      (node (ref "C1") (pin "1") (pinfunction "1_1") (pintype "passive"))
      (node (ref "C12") (pin "2") (pinfunction "2_2") (pintype "passive"))
      (node (ref "C7") (pin "1") (pinfunction "1_1") (pintype "passive"))
      (node (ref "D1") (pin "1") (pinfunction "A_1") (pintype "passive"))
      (node (ref "J1") (pin "4") (pinfunction "VCC_4") (pintype "power_in"))
      (node (ref "J2") (pin "1") (pinfunction "VCC_1") (pintype "passive"))
      (node (ref "J3") (pin "4") (pinfunction "VCC_4") (pintype "power_in"))
      (node (ref "P1") (pin "1") (pinfunction "1_1") (pintype "passive"))
      (node (ref "P2") (pin "18") (pinfunction "18_18") (pintype "passive"))
      (node (ref "R16") (pin "2") (pinfunction "2_2") (pintype "passive"))
      (node (ref "R18") (pin "2") (pinfunction "2_2") (pintype "passive"))
      (node (ref "R20") (pin "2") (pinfunction "2_2") (pintype "passive"))
      (node (ref "R23") (pin "2") (pinfunction "2_2") (pintype "passive"))
      (node (ref "U1") (pin "3") (pinfunction "Vin_3") (pintype "passive"))
      (node (ref "U3") (pin "3") (pinfunction "Vin_3") (pintype "passive"))
      (node (ref "U5") (pin "20") (pinfunction "VCC_20") (pintype "power_in"))
    )
    (net (code "148") (name "GND") (class "Default")
      (node (ref "1") (pin "10") (pinfunction "10_10") (pintype "passive"))
      (node (ref "1") (pin "5") (pinfunction "5_5") (pintype "passive"))
      (node (ref "1") (pin "6") (pinfunction "6_6") (pintype "passive"))
      (node (ref "1") (pin "7") (pinfunction "7_7") (pintype "passive"))
      (node (ref "1") (pin "8") (pinfunction "8_8") (pintype "passive"))
      (node (ref "C1") (pin "2") (pinfunction "2_2") (pintype "passive"))
      (node (ref "C10") (pin "1") (pinfunction "1_1") (pintype "passive"))
      (node (ref "C11") (pin "1") (pinfunction "1_1") (pintype "passive"))
      (node (ref "C12") (pin "1") (pinfunction "1_1") (pintype "passive"))
      (node (ref "C13") (pin "1") (pinfunction "1_1") (pintype "passive"))
      (node (ref "C14") (pin "1") (pinfunction "1_1") (pintype "passive"))
      (node (ref "C15") (pin "1") (pinfunction "1_1") (pintype "passive"))
      (node (ref "C16") (pin "1") (pinfunction "1_1") (pintype "passive"))
      (node (ref "C17") (pin "1") (pinfunction "1_1") (pintype "passive"))
      (node (ref "C18") (pin "1") (pinfunction "1_1") (pintype "passive"))
      (node (ref "C19") (pin "1") (pinfunction "1_1") (pintype "passive"))
      (node (ref "C2") (pin "2") (pinfunction "2_2") (pintype "passive"))
      (node (ref "C20") (pin "1") (pinfunction "1_1") (pintype "passive"))
      (node (ref "C21") (pin "1") (pinfunction "1_1") (pintype "passive"))
      (node (ref "C22") (pin "1") (pinfunction "1_1") (pintype "passive"))
      (node (ref "C23") (pin "1") (pinfunction "1_1") (pintype "passive"))
      (node (ref "C24") (pin "1") (pinfunction "1_1") (pintype "passive"))
      (node (ref "C25") (pin "1") (pinfunction "1_1") (pintype "passive"))
      (node (ref "C26") (pin "1") (pinfunction "1_1") (pintype "passive"))
      (node (ref "C27") (pin "1") (pinfunction "1_1") (pintype "passive"))
      (node (ref "C28") (pin "1") (pinfunction "1_1") (pintype "passive"))
      (node (ref "C29") (pin "1") (pinfunction "1_1") (pintype "passive"))
      (node (ref "C3") (pin "2") (pinfunction "2_2") (pintype "passive"))
      (node (ref "C30") (pin "1") (pinfunction "1_1") (pintype "passive"))
      (node (ref "C31") (pin "1") (pinfunction "1_1") (pintype "passive"))
      (node (ref "C32") (pin "1") (pinfunction "1_1") (pintype "passive"))
      (node (ref "C33") (pin "1") (pinfunction "1_1") (pintype "passive"))
      (node (ref "C34") (pin "1") (pinfunction "1_1") (pintype "passive"))
      (node (ref "C35") (pin "1") (pinfunction "1_1") (pintype "passive"))
      (node (ref "C36") (pin "1") (pinfunction "1_1") (pintype "passive"))
      (node (ref "C37") (pin "1") (pinfunction "1_1") (pintype "passive"))
      (node (ref "C38") (pin "1") (pinfunction "1_1") (pintype "passive"))
      (node (ref "C39") (pin "1") (pinfunction "1_1") (pintype "passive"))
      (node (ref "C4") (pin "2") (pinfunction "2_2") (pintype "passive"))
      (node (ref "C40") (pin "1") (pinfunction "1_1") (pintype "passive"))
      (node (ref "C41") (pin "1") (pinfunction "1_1") (pintype "passive"))
      (node (ref "C42") (pin "1") (pinfunction "1_1") (pintype "passive"))
      (node (ref "C43") (pin "1") (pinfunction "1_1") (pintype "passive"))
      (node (ref "C44") (pin "1") (pinfunction "1_1") (pintype "passive"))
      (node (ref "C45") (pin "1") (pinfunction "1_1") (pintype "passive"))
      (node (ref "C46") (pin "1") (pinfunction "1_1") (pintype "passive"))
      (node (ref "C47") (pin "1") (pinfunction "1_1") (pintype "passive"))
      (node (ref "C48") (pin "1") (pinfunction "1_1") (pintype "passive"))
      (node (ref "C49") (pin "1") (pinfunction "1_1") (pintype "passive"))
      (node (ref "C5") (pin "2") (pinfunction "2_2") (pintype "passive"))
      (node (ref "C50") (pin "1") (pinfunction "1_1") (pintype "passive"))
      (node (ref "C51") (pin "1") (pinfunction "1_1") (pintype "passive"))
      (node (ref "C52") (pin "1") (pinfunction "1_1") (pintype "passive"))
      (node (ref "C53") (pin "1") (pinfunction "1_1") (pintype "passive"))
      (node (ref "C54") (pin "1") (pinfunction "1_1") (pintype "passive"))
      (node (ref "C55") (pin "1") (pinfunction "1_1") (pintype "passive"))
      (node (ref "C56") (pin "1") (pinfunction "1_1") (pintype "passive"))
      (node (ref "C57") (pin "1") (pinfunction "1_1") (pintype "passive"))
      (node (ref "C58") (pin "1") (pinfunction "1_1") (pintype "passive"))
      (node (ref "C59") (pin "1") (pinfunction "1_1") (pintype "passive"))
      (node (ref "C6") (pin "1") (pinfunction "1_1") (pintype "passive"))
      (node (ref "C60") (pin "1") (pinfunction "1_1") (pintype "passive"))
      (node (ref "C61") (pin "1") (pinfunction "1_1") (pintype "passive"))
      (node (ref "C62") (pin "1") (pinfunction "1_1") (pintype "passive"))
      (node (ref "C63") (pin "1") (pinfunction "1_1") (pintype "passive"))
      (node (ref "C64") (pin "1") (pinfunction "1_1") (pintype "passive"))
      (node (ref "C65") (pin "1") (pinfunction "1_1") (pintype "passive"))
      (node (ref "C66") (pin "1") (pinfunction "1_1") (pintype "passive"))
      (node (ref "C67") (pin "1") (pinfunction "1_1") (pintype "passive"))
      (node (ref "C68") (pin "1") (pinfunction "1_1") (pintype "passive"))
      (node (ref "C69") (pin "1") (pinfunction "1_1") (pintype "passive"))
      (node (ref "C7") (pin "2") (pinfunction "2_2") (pintype "passive"))
      (node (ref "C8") (pin "2") (pinfunction "2_2") (pintype "passive"))
      (node (ref "C9") (pin "1") (pinfunction "1_1") (pintype "passive"))
      (node (ref "J1") (pin "0") (pinfunction "Shield_0") (pintype "passive"))
      (node (ref "J1") (pin "3") (pinfunction "GND_3") (pintype "power_in"))
      (node (ref "J2") (pin "5") (pinfunction "GND_5") (pintype "passive"))
      (node (ref "J2") (pin "S") (pinfunction "Shield_S") (pintype "passive"))
      (node (ref "J3") (pin "0") (pinfunction "Shield_0") (pintype "passive"))
      (node (ref "J3") (pin "3") (pinfunction "GND_3") (pintype "power_in"))
      (node (ref "J4") (pin "6") (pinfunction "6_6") (pintype "bidirectional"))
      (node (ref "J5") (pin "10") (pinfunction "10_10") (pintype "passive"))
      (node (ref "J5") (pin "2") (pinfunction "2_2") (pintype "passive"))
      (node (ref "P1") (pin "5") (pinfunction "5_5") (pintype "passive"))
      (node (ref "P2") (pin "13") (pinfunction "13_13") (pintype "passive"))
      (node (ref "P2") (pin "16") (pinfunction "16_16") (pintype "passive"))
      (node (ref "P3") (pin "7") (pinfunction "7_7") (pintype "passive"))
      (node (ref "P4") (pin "10") (pinfunction "10_10") (pintype "passive"))
      (node (ref "R1") (pin "1") (pinfunction "1_1") (pintype "passive"))
      (node (ref "R2") (pin "1") (pinfunction "1_1") (pintype "passive"))
      (node (ref "R21") (pin "1") (pinfunction "1_1") (pintype "passive"))
      (node (ref "R24") (pin "1") (pinfunction "1_1") (pintype "passive"))
      (node (ref "R3") (pin "1") (pinfunction "1_1") (pintype "passive"))
      (node (ref "R30") (pin "1") (pinfunction "1_1") (pintype "passive"))
      (node (ref "R49") (pin "1") (pinfunction "1_1") (pintype "passive"))
      (node (ref "R50") (pin "1") (pinfunction "1_1") (pintype "passive"))
      (node (ref "R51") (pin "1") (pinfunction "1_1") (pintype "passive"))
      (node (ref "R55") (pin "2") (pinfunction "2_2") (pintype "passive"))
      (node (ref "R6") (pin "1") (pinfunction "1_1") (pintype "passive"))
      (node (ref "R61") (pin "2") (pinfunction "2_2") (pintype "passive"))
      (node (ref "R7") (pin "1") (pinfunction "1_1") (pintype "passive"))
      (node (ref "R8") (pin "1") (pinfunction "1_1") (pintype "passive"))
      (node (ref "U10") (pin "102") (pinfunction "GND_102") (pintype "power_in"))
      (node (ref "U10") (pin "105") (pinfunction "GND_105") (pintype "power_in"))
      (node (ref "U10") (pin "107") (pinfunction "IO,_VREFB4N0_107") (pintype "bidirectional"))
      (node (ref "U10") (pin "11") (pinfunction "GND_11") (pintype "power_in"))
      (node (ref "U10") (pin "116") (pinfunction "GND_116") (pintype "power_in"))
      (node (ref "U10") (pin "122") (pinfunction "GNDA4_122") (pintype "power_in"))
      (node (ref "U10") (pin "125") (pinfunction "GND_125") (pintype "power_in"))
      (node (ref "U10") (pin "130") (pinfunction "GND_130") (pintype "power_in"))
      (node (ref "U10") (pin "133") (pinfunction "IO,_VREFB5N0_133") (pintype "bidirectional"))
      (node (ref "U10") (pin "138") (pinfunction "GND_138") (pintype "power_in"))
      (node (ref "U10") (pin "141") (pinfunction "GND_141") (pintype "power_in"))
      (node (ref "U10") (pin "149") (pinfunction "CLK7,_DIFFCLK_3n_149") (pintype "input"))
      (node (ref "U10") (pin "150") (pinfunction "CLK6,_DIFFCLK_3p_150") (pintype "input"))
      (node (ref "U10") (pin "151") (pinfunction "CLK5,_DIFFCLK_2n_151") (pintype "input"))
      (node (ref "U10") (pin "152") (pinfunction "CLK4,_DIFFCLK_2p_152") (pintype "input"))
      (node (ref "U10") (pin "156") (pinfunction "GND_156") (pintype "power_in"))
      (node (ref "U10") (pin "16") (pinfunction "GND_16") (pintype "power_in"))
      (node (ref "U10") (pin "165") (pinfunction "GND_165") (pintype "power_in"))
      (node (ref "U10") (pin "172") (pinfunction "GND_172") (pintype "power_in"))
      (node (ref "U10") (pin "175") (pinfunction "GND_175") (pintype "power_in"))
      (node (ref "U10") (pin "179") (pinfunction "GNDA2_179") (pintype "power_in"))
      (node (ref "U10") (pin "191") (pinfunction "GND_191") (pintype "power_in"))
      (node (ref "U10") (pin "193") (pinfunction "GND_193") (pintype "power_in"))
      (node (ref "U10") (pin "199") (pinfunction "GND_199") (pintype "power_in"))
      (node (ref "U10") (pin "2") (pinfunction "GNDA3_2") (pintype "power_in"))
      (node (ref "U10") (pin "20") (pinfunction "GND_20") (pintype "power_in"))
      (node (ref "U10") (pin "205") (pinfunction "GND_205") (pintype "power_in"))
      (node (ref "U10") (pin "208") (pinfunction "GND_208") (pintype "power_in"))
      (node (ref "U10") (pin "209") (pinfunction "CLK8,_DIFFCLK_5n_209") (pintype "input"))
      (node (ref "U10") (pin "210") (pinfunction "CLK9,_DIFFCLK_5p_210") (pintype "input"))
      (node (ref "U10") (pin "211") (pinfunction "CLK10,_DIFFCLK_4n_211") (pintype "input"))
      (node (ref "U10") (pin "212") (pinfunction "CLK11,_DIFFCLK_4p_212") (pintype "input"))
      (node (ref "U10") (pin "215") (pinfunction "GND_215") (pintype "power_in"))
      (node (ref "U10") (pin "222") (pinfunction "GND_222") (pintype "power_in"))
      (node (ref "U10") (pin "227") (pinfunction "GND_227") (pintype "power_in"))
      (node (ref "U10") (pin "229") (pinfunction "GND_229") (pintype "power_in"))
      (node (ref "U10") (pin "32") (pinfunction "CLK1,_DIFFCLK_0n_32") (pintype "input"))
      (node (ref "U10") (pin "33") (pinfunction "CLK2,_DIFFCLK_1p_33") (pintype "input"))
      (node (ref "U10") (pin "34") (pinfunction "CLK3,_DIFFCLK_1n_34") (pintype "input"))
      (node (ref "U10") (pin "36") (pinfunction "GND_36") (pintype "power_in"))
      (node (ref "U10") (pin "42") (pinfunction "GND_42") (pintype "power_in"))
      (node (ref "U10") (pin "46") (pinfunction "IO,_VREFB2N0_46") (pintype "bidirectional"))
      (node (ref "U10") (pin "48") (pinfunction "GND_48") (pintype "power_in"))
      (node (ref "U10") (pin "54") (pinfunction "GND_54") (pintype "power_in"))
      (node (ref "U10") (pin "59") (pinfunction "GNDA1_59") (pintype "power_in"))
      (node (ref "U10") (pin "62") (pinfunction "GND_62") (pintype "power_in"))
      (node (ref "U10") (pin "67") (pinfunction "GND_67") (pintype "power_in"))
      (node (ref "U10") (pin "75") (pinfunction "GND_75") (pintype "power_in"))
      (node (ref "U10") (pin "76") (pinfunction "IO,_VREFB3N0_76") (pintype "bidirectional"))
      (node (ref "U10") (pin "79") (pinfunction "GND_79") (pintype "power_in"))
      (node (ref "U10") (pin "8") (pinfunction "GND_8") (pintype "power_in"))
      (node (ref "U10") (pin "86") (pinfunction "GND_86") (pintype "power_in"))
      (node (ref "U10") (pin "89") (pinfunction "CLK15,_DIFFCLK_6p_89") (pintype "input"))
      (node (ref "U10") (pin "90") (pinfunction "CLK14,_DIFFCLK_6n_90") (pintype "input"))
      (node (ref "U10") (pin "91") (pinfunction "CLK13,_DIFFCLK_7p_91") (pintype "input"))
      (node (ref "U10") (pin "92") (pinfunction "CLK12,_DIFFCLK_7n_92") (pintype "input"))
      (node (ref "U10") (pin "97") (pinfunction "GND_97") (pintype "power_in"))
      (node (ref "U11") (pin "4") (pinfunction "VSS_4") (pintype "power_in"))
      (node (ref "U12") (pin "12") (pinfunction "VSSQ_12") (pintype "power_in"))
      (node (ref "U12") (pin "14") (pinfunction "NC_14") (pintype "passive"))
      (node (ref "U12") (pin "30") (pinfunction "NC_30") (pintype "passive"))
      (node (ref "U12") (pin "32") (pinfunction "VSSQ_32") (pintype "power_in"))
      (node (ref "U12") (pin "38") (pinfunction "VSSQ_38") (pintype "power_in"))
      (node (ref "U12") (pin "44") (pinfunction "VSS_44") (pintype "power_in"))
      (node (ref "U12") (pin "46") (pinfunction "VSSQ_46") (pintype "power_in"))
      (node (ref "U12") (pin "52") (pinfunction "VSSQ_52") (pintype "power_in"))
      (node (ref "U12") (pin "57") (pinfunction "NC_57") (pintype "passive"))
      (node (ref "U12") (pin "58") (pinfunction "VSS_58") (pintype "power_in"))
      (node (ref "U12") (pin "6") (pinfunction "VSSQ_6") (pintype "power_in"))
      (node (ref "U12") (pin "69") (pinfunction "NC_69") (pintype "passive"))
      (node (ref "U12") (pin "70") (pinfunction "NU_70") (pintype "passive"))
      (node (ref "U12") (pin "72") (pinfunction "VSS_72") (pintype "power_in"))
      (node (ref "U12") (pin "73") (pinfunction "NC_73") (pintype "passive"))
      (node (ref "U12") (pin "78") (pinfunction "VSSQ_78") (pintype "power_in"))
      (node (ref "U12") (pin "84") (pinfunction "VSSQ_84") (pintype "power_in"))
      (node (ref "U12") (pin "86") (pinfunction "VSS_86") (pintype "power_in"))
      (node (ref "U2") (pin "1") (pinfunction "GND_1") (pintype "passive"))
      (node (ref "U4") (pin "4") (pinfunction "VSS_4") (pintype "power_in"))
      (node (ref "U5") (pin "18") (pinfunction "GND_18") (pintype "power_in"))
      (node (ref "U5") (pin "21") (pinfunction "GND_21") (pintype "power_in"))
      (node (ref "U5") (pin "25") (pinfunction "AGND_25") (pintype "power_in"))
      (node (ref "U5") (pin "26") (pinfunction "TEST_26") (pintype "input"))
      (node (ref "U5") (pin "7") (pinfunction "GND_7") (pintype "power_in"))
      (node (ref "Y1") (pin "2") (pinfunction "GND_2") (pintype "power_in"))
    )
    (net (code "149") (name "Net-(D1-K)") (class "Default")
      (node (ref "D1") (pin "2") (pinfunction "K_2") (pintype "passive"))
      (node (ref "R1") (pin "2") (pinfunction "2_2") (pintype "passive"))
    )
    (net (code "150") (name "Net-(D2-K)") (class "Default")
      (node (ref "D2") (pin "2") (pinfunction "K_2") (pintype "passive"))
      (node (ref "R2") (pin "2") (pinfunction "2_2") (pintype "passive"))
    )
    (net (code "151") (name "Net-(D3-K)") (class "Default")
      (node (ref "D3") (pin "2") (pinfunction "K_2") (pintype "passive"))
      (node (ref "R3") (pin "2") (pinfunction "2_2") (pintype "passive"))
    )
    (net (code "152") (name "Net-(D4-K)") (class "Default")
      (node (ref "D4") (pin "2") (pinfunction "K_2") (pintype "passive"))
      (node (ref "R7") (pin "2") (pinfunction "2_2") (pintype "passive"))
    )
    (net (code "153") (name "Net-(D9-K)") (class "Default")
      (node (ref "D9") (pin "2") (pinfunction "K_2") (pintype "passive"))
      (node (ref "R21") (pin "2") (pinfunction "2_2") (pintype "passive"))
    )
    (net (code "154") (name "Net-(D10-K)") (class "Default")
      (node (ref "D10") (pin "2") (pinfunction "K_2") (pintype "passive"))
      (node (ref "R24") (pin "2") (pinfunction "2_2") (pintype "passive"))
    )
    (net (code "155") (name "Net-(U1-ADJ)") (class "Default")
      (node (ref "R4") (pin "1") (pinfunction "1_1") (pintype "passive"))
      (node (ref "R6") (pin "2") (pinfunction "2_2") (pintype "passive"))
      (node (ref "U1") (pin "1") (pinfunction "ADJ_1") (pintype "passive"))
    )
    (net (code "156") (name "Net-(U3-ADJ)") (class "Default")
      (node (ref "R5") (pin "1") (pinfunction "1_1") (pintype "passive"))
      (node (ref "R8") (pin "2") (pinfunction "2_2") (pintype "passive"))
      (node (ref "U3") (pin "1") (pinfunction "ADJ_1") (pintype "passive"))
    )
    (net (code "157") (name "Net-(U5-3V3OUT)") (class "Default")
      (node (ref "C5") (pin "1") (pinfunction "1_1") (pintype "passive"))
      (node (ref "U5") (pin "17") (pinfunction "3V3OUT_17") (pintype "output"))
    )
    (net (code "158") (name "Net-(U5-CBUS3)") (class "Default")
      (node (ref "R13") (pin "1") (pinfunction "1_1") (pintype "passive"))
      (node (ref "U5") (pin "14") (pinfunction "CBUS3_14") (pintype "bidirectional"))
    )
    (net (code "159") (name "Net-(U5-~{RESET})") (class "Default")
      (node (ref "R14") (pin "2") (pinfunction "2_2") (pintype "passive"))
      (node (ref "U5") (pin "19") (pinfunction "~{RESET}_19") (pintype "input"))
    )
    (net (code "160") (name "Net-(U10I-CLK0,_DIFFCLK_0p)") (class "Default")
      (node (ref "R59") (pin "1") (pinfunction "1_1") (pintype "passive"))
      (node (ref "U10") (pin "31") (pinfunction "CLK0,_DIFFCLK_0p_31") (pintype "input"))
    )
    (net (code "161") (name "Net-(U11-HOLD#)") (class "Default")
      (node (ref "R31") (pin "1") (pinfunction "1_1") (pintype "passive"))
      (node (ref "U11") (pin "3") (pinfunction "W#_3") (pintype "input"))
      (node (ref "U11") (pin "7") (pinfunction "HOLD#_7") (pintype "input"))
    )
    (net (code "162") (name "Vjtag") (class "Default")
      (node (ref "J5") (pin "4") (pinfunction "4_4") (pintype "passive"))
      (node (ref "R39") (pin "1") (pinfunction "1_1") (pintype "passive"))
      (node (ref "R41") (pin "1") (pinfunction "1_1") (pintype "passive"))
    )
    (net (code "163") (name "unconnected-(1-Pad4)") (class "Default")
      (node (ref "1") (pin "4") (pinfunction "4_4") (pintype "passive"))
    )
    (net (code "164") (name "unconnected-(1-Pad9)") (class "Default")
      (node (ref "1") (pin "9") (pinfunction "9_9") (pintype "passive"))
    )
    (net (code "165") (name "unconnected-(1-Pad11)") (class "Default")
      (node (ref "1") (pin "11") (pinfunction "11_11") (pintype "passive"))
    )
    (net (code "166") (name "unconnected-(1-Pad12)") (class "Default")
      (node (ref "1") (pin "12") (pinfunction "12_12") (pintype "passive"))
    )
    (net (code "167") (name "unconnected-(1-Pad15)") (class "Default")
      (node (ref "1") (pin "15") (pinfunction "15_15") (pintype "passive"))
    )
    (net (code "168") (name "unconnected-(D5-Pad1)") (class "Default")
      (node (ref "D5") (pin "1") (pintype "passive"))
    )
    (net (code "169") (name "unconnected-(D6-Pad1)") (class "Default")
      (node (ref "D6") (pin "1") (pintype "passive"))
    )
    (net (code "170") (name "unconnected-(D7-Pad1)") (class "Default")
      (node (ref "D7") (pin "1") (pintype "passive"))
    )
    (net (code "171") (name "unconnected-(D8-Pad1)") (class "Default")
      (node (ref "D8") (pin "1") (pintype "passive"))
    )
    (net (code "172") (name "unconnected-(J2-ID-Pad4)") (class "Default")
      (node (ref "J2") (pin "4") (pinfunction "ID_4") (pintype "passive"))
    )
    (net (code "173") (name "unconnected-(J5-Pad6)") (class "Default")
      (node (ref "J5") (pin "6") (pinfunction "6_6") (pintype "passive"))
    )
    (net (code "174") (name "unconnected-(J5-Pad7)") (class "Default")
      (node (ref "J5") (pin "7") (pinfunction "7_7") (pintype "passive"))
    )
    (net (code "175") (name "unconnected-(J5-Pad8)") (class "Default")
      (node (ref "J5") (pin "8") (pinfunction "8_8") (pintype "passive"))
    )
    (net (code "176") (name "unconnected-(P4-Pad1)") (class "Default")
      (node (ref "P4") (pin "1") (pinfunction "1_1") (pintype "passive"))
    )
    (net (code "177") (name "unconnected-(P4-Pad3)") (class "Default")
      (node (ref "P4") (pin "3") (pinfunction "3_3") (pintype "passive"))
    )
    (net (code "178") (name "unconnected-(U5-CBUS0-Pad23)") (class "Default")
      (node (ref "U5") (pin "23") (pinfunction "CBUS0_23") (pintype "bidirectional"))
    )
    (net (code "179") (name "unconnected-(U5-CBUS1-Pad22)") (class "Default")
      (node (ref "U5") (pin "22") (pinfunction "CBUS1_22") (pintype "bidirectional"))
    )
    (net (code "180") (name "unconnected-(U5-CBUS2-Pad13)") (class "Default")
      (node (ref "U5") (pin "13") (pinfunction "CBUS2_13") (pintype "bidirectional"))
    )
    (net (code "181") (name "unconnected-(U5-CBUS4-Pad12)") (class "Default")
      (node (ref "U5") (pin "12") (pinfunction "CBUS4_12") (pintype "bidirectional"))
    )
    (net (code "182") (name "unconnected-(U5-NC-Pad8)") (class "Default")
      (node (ref "U5") (pin "8") (pinfunction "NC_8") (pintype "passive"))
    )
    (net (code "183") (name "unconnected-(U5-NC-Pad24)") (class "Default")
      (node (ref "U5") (pin "24") (pinfunction "NC_24") (pintype "passive"))
    )
    (net (code "184") (name "unconnected-(U5-OSCI-Pad27)") (class "Default")
      (node (ref "U5") (pin "27") (pinfunction "OSCI_27") (pintype "input"))
    )
    (net (code "185") (name "unconnected-(U5-OSCO-Pad28)") (class "Default")
      (node (ref "U5") (pin "28") (pinfunction "OSCO_28") (pintype "output"))
    )
    (net (code "186") (name "unconnected-(U5-~{CTS}-Pad11)") (class "Default")
      (node (ref "U5") (pin "11") (pinfunction "~{CTS}_11") (pintype "input"))
    )
    (net (code "187") (name "unconnected-(U5-~{DCD}-Pad10)") (class "Default")
      (node (ref "U5") (pin "10") (pinfunction "~{DCD}_10") (pintype "input"))
    )
    (net (code "188") (name "unconnected-(U5-~{DSR}-Pad9)") (class "Default")
      (node (ref "U5") (pin "9") (pinfunction "~{DSR}_9") (pintype "input"))
    )
    (net (code "189") (name "unconnected-(U5-~{DTR}-Pad2)") (class "Default")
      (node (ref "U5") (pin "2") (pinfunction "~{DTR}_2") (pintype "output"))
    )
    (net (code "190") (name "unconnected-(U5-~{RI}-Pad6)") (class "Default")
      (node (ref "U5") (pin "6") (pinfunction "~{RI}_6") (pintype "input"))
    )
    (net (code "191") (name "unconnected-(U5-~{RTS}-Pad3)") (class "Default")
      (node (ref "U5") (pin "3") (pinfunction "~{RTS}_3") (pintype "output"))
    )
    (net (code "192") (name "unconnected-(U10A-IO,_(DQS2L{slash}CQ3L,CDPCLK0)-Pad9)") (class "Default")
      (node (ref "U10") (pin "9") (pinfunction "IO,_(DQS2L/CQ3L,CDPCLK0)_9") (pintype "bidirectional"))
    )
    (net (code "193") (name "unconnected-(U10A-IO,_DIFFIO_L6n-Pad22)") (class "Default")
      (node (ref "U10") (pin "22") (pinfunction "IO,_DIFFIO_L6n_22") (pintype "bidirectional"))
    )
    (net (code "194") (name "unconnected-(U10A-IO,_DIFFIO_L6p,_(DQS0L{slash}CQ1L,DPCLK0)-Pad21)") (class "Default")
      (node (ref "U10") (pin "21") (pinfunction "IO,_DIFFIO_L6p,_(DQS0L/CQ1L,DPCLK0)_21") (pintype "bidirectional"))
    )
    (net (code "195") (name "unconnected-(U10A-IO,_VREFB1N0-Pad13)") (class "Default")
      (node (ref "U10") (pin "13") (pinfunction "IO,_VREFB1N0_13") (pintype "bidirectional"))
    )
    (net (code "196") (name "unconnected-(U10A-IO-Pad18)") (class "Default")
      (node (ref "U10") (pin "18") (pinfunction "IO_18") (pintype "bidirectional"))
    )
    (net (code "197") (name "unconnected-(U10F-IO,_VREFB6N0-Pad169)") (class "Default")
      (node (ref "U10") (pin "169") (pinfunction "IO,_VREFB6N0_169") (pintype "bidirectional"))
    )
    (net (code "198") (name "unconnected-(U10G-IO,_(PADD0),_(DQ5T)-Pad194)") (class "Default")
      (node (ref "U10") (pin "194") (pinfunction "IO,_(PADD0),_(DQ5T)_194") (pintype "bidirectional"))
    )
    (net (code "199") (name "unconnected-(U10G-IO,_DIFFIO_T19n,_(PADD1)-Pad196)") (class "Default")
      (node (ref "U10") (pin "196") (pinfunction "IO,_DIFFIO_T19n,_(PADD1)_196") (pintype "bidirectional"))
    )
    (net (code "200") (name "unconnected-(U10G-IO,_DIFFIO_T23n-Pad182)") (class "Default")
      (node (ref "U10") (pin "182") (pinfunction "IO,_DIFFIO_T23n_182") (pintype "bidirectional"))
    )
    (net (code "201") (name "unconnected-(U10G-IO,_DIFFIO_T23p,_(DQS0T{slash}CQ1T,CDPCLK6)-Pad183)") (class "Default")
      (node (ref "U10") (pin "183") (pinfunction "IO,_DIFFIO_T23p,_(DQS0T/CQ1T,CDPCLK6)_183") (pintype "bidirectional"))
    )
    (net (code "202") (name "unconnected-(U10G-IO,_PLL2_CLKOUTn-Pad185)") (class "Default")
      (node (ref "U10") (pin "185") (pinfunction "IO,_PLL2_CLKOUTn_185") (pintype "bidirectional"))
    )
    (net (code "203") (name "unconnected-(U10G-IO,_PLL2_CLKOUTp-Pad186)") (class "Default")
      (node (ref "U10") (pin "186") (pinfunction "IO,_PLL2_CLKOUTp_186") (pintype "bidirectional"))
    )
    (net (code "204") (name "unconnected-(U10G-IO,_RDN4-Pad188)") (class "Default")
      (node (ref "U10") (pin "188") (pinfunction "IO,_RDN4_188") (pintype "bidirectional"))
    )
    (net (code "205") (name "unconnected-(U10G-IO,_RUP4-Pad187)") (class "Default")
      (node (ref "U10") (pin "187") (pinfunction "IO,_RUP4_187") (pintype "bidirectional"))
    )
    (net (code "206") (name "unconnected-(U10G-IO,_VREFB7N0-Pad195)") (class "Default")
      (node (ref "U10") (pin "195") (pinfunction "IO,_VREFB7N0_195") (pintype "bidirectional"))
    )
    (net (code "207") (name "unconnected-(U10G-IO-Pad181)") (class "Default")
      (node (ref "U10") (pin "181") (pinfunction "IO_181") (pintype "bidirectional"))
    )
    (net (code "208") (name "unconnected-(U10G-IO-Pad184)") (class "Default")
      (node (ref "U10") (pin "184") (pinfunction "IO_184") (pintype "bidirectional"))
    )
    (net (code "209") (name "unconnected-(U10G-IO-Pad189)") (class "Default")
      (node (ref "U10") (pin "189") (pinfunction "IO_189") (pintype "bidirectional"))
    )
  )
)
